# Altium.net
KiCad netlist of a schematic drawn in Altium Designer
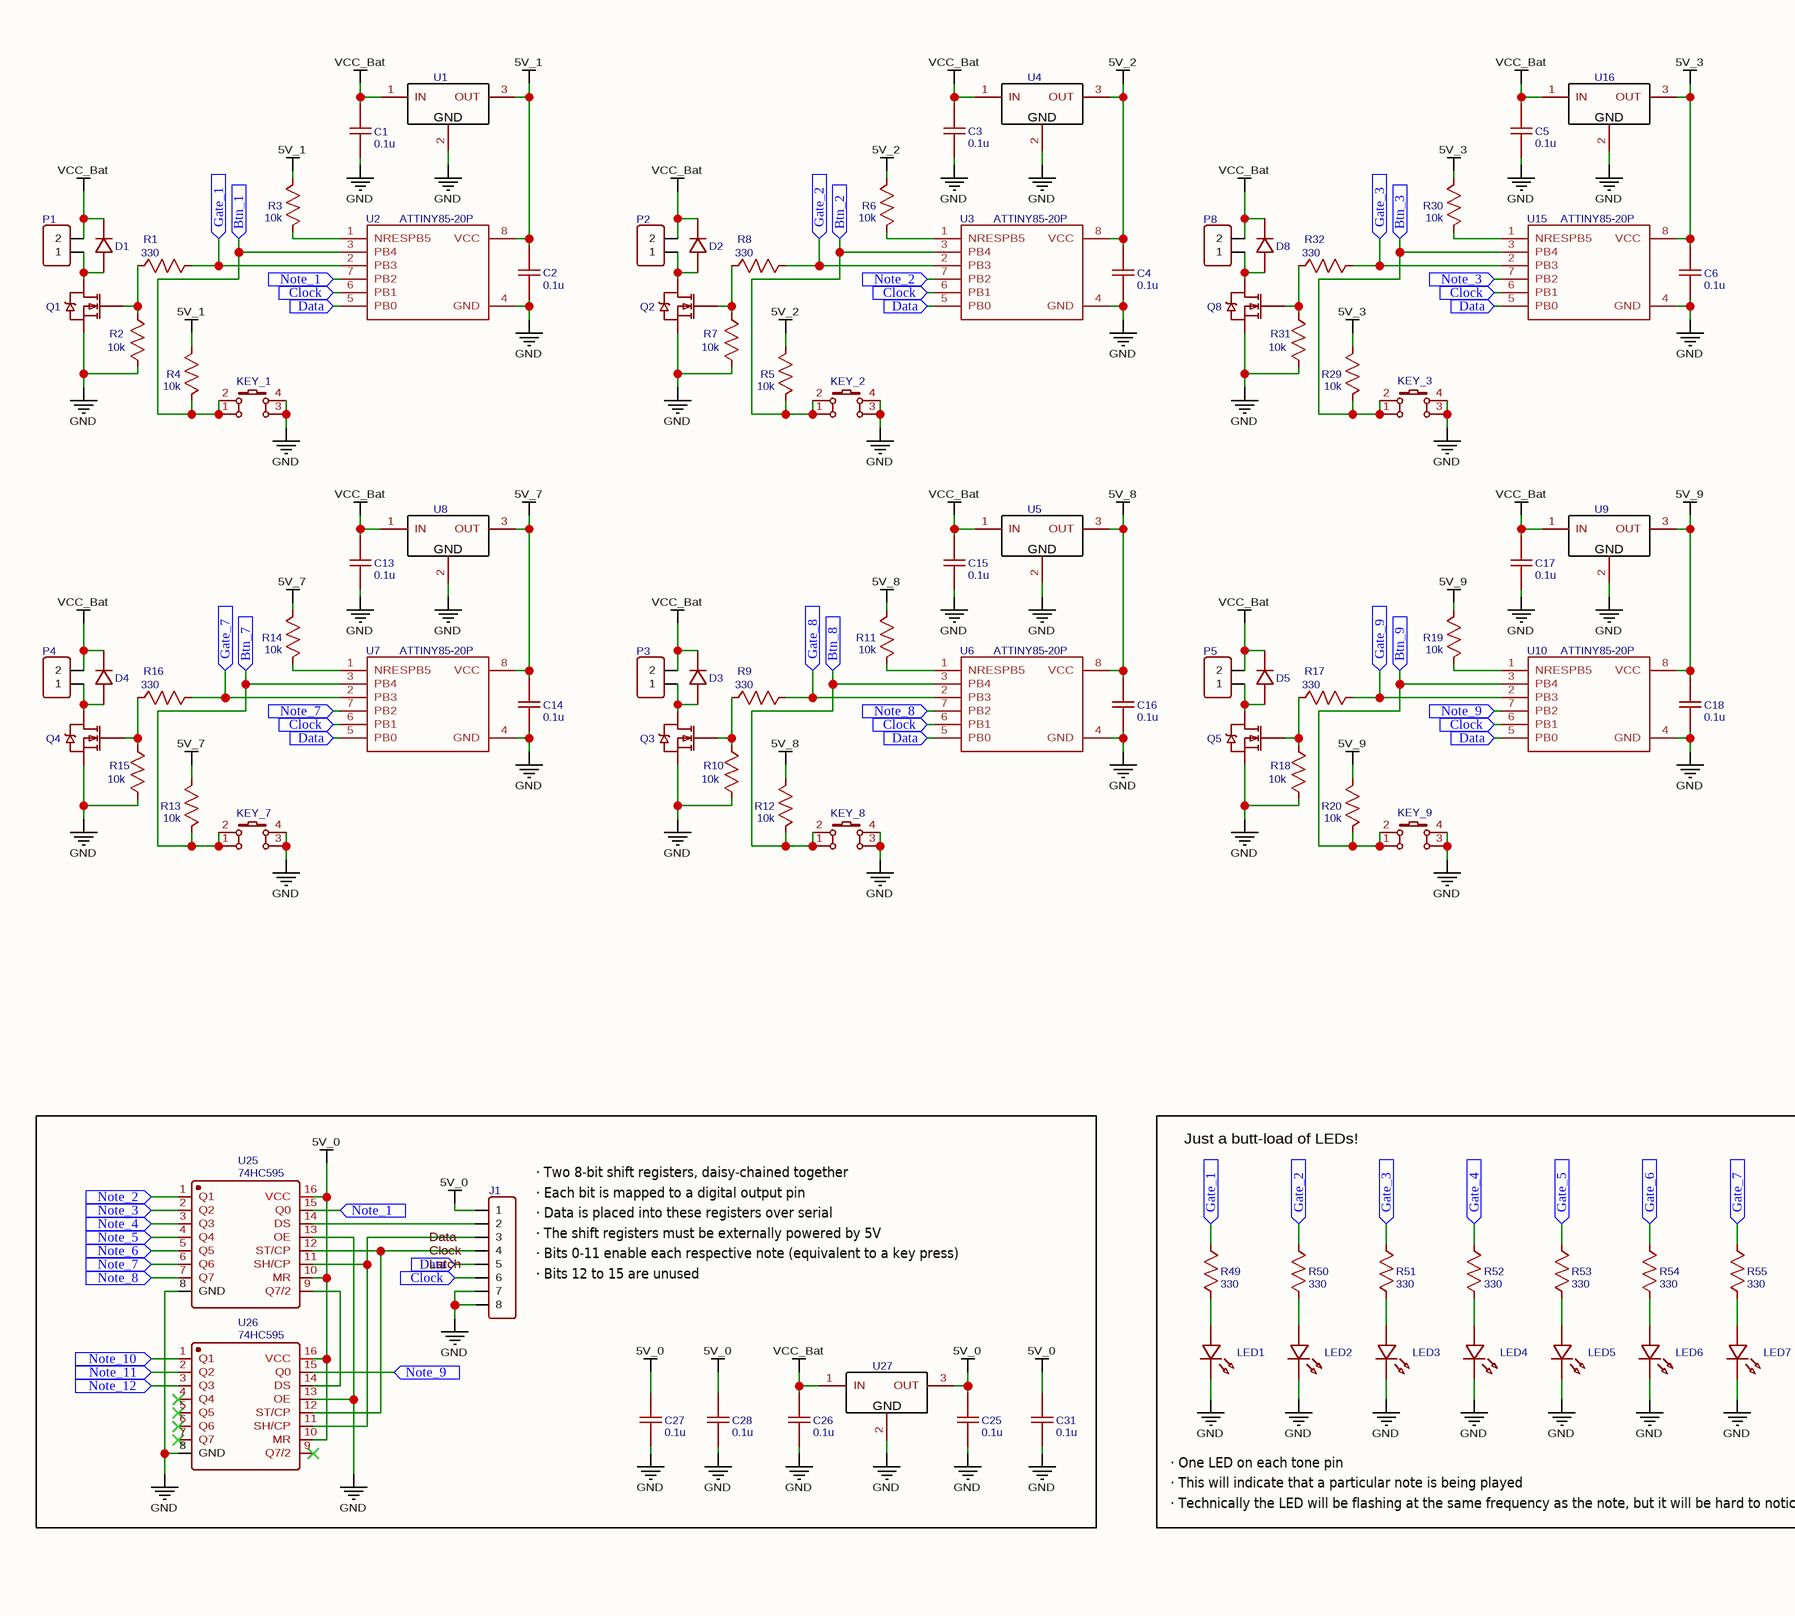
[diagram p0: Altium.schdoc, left]
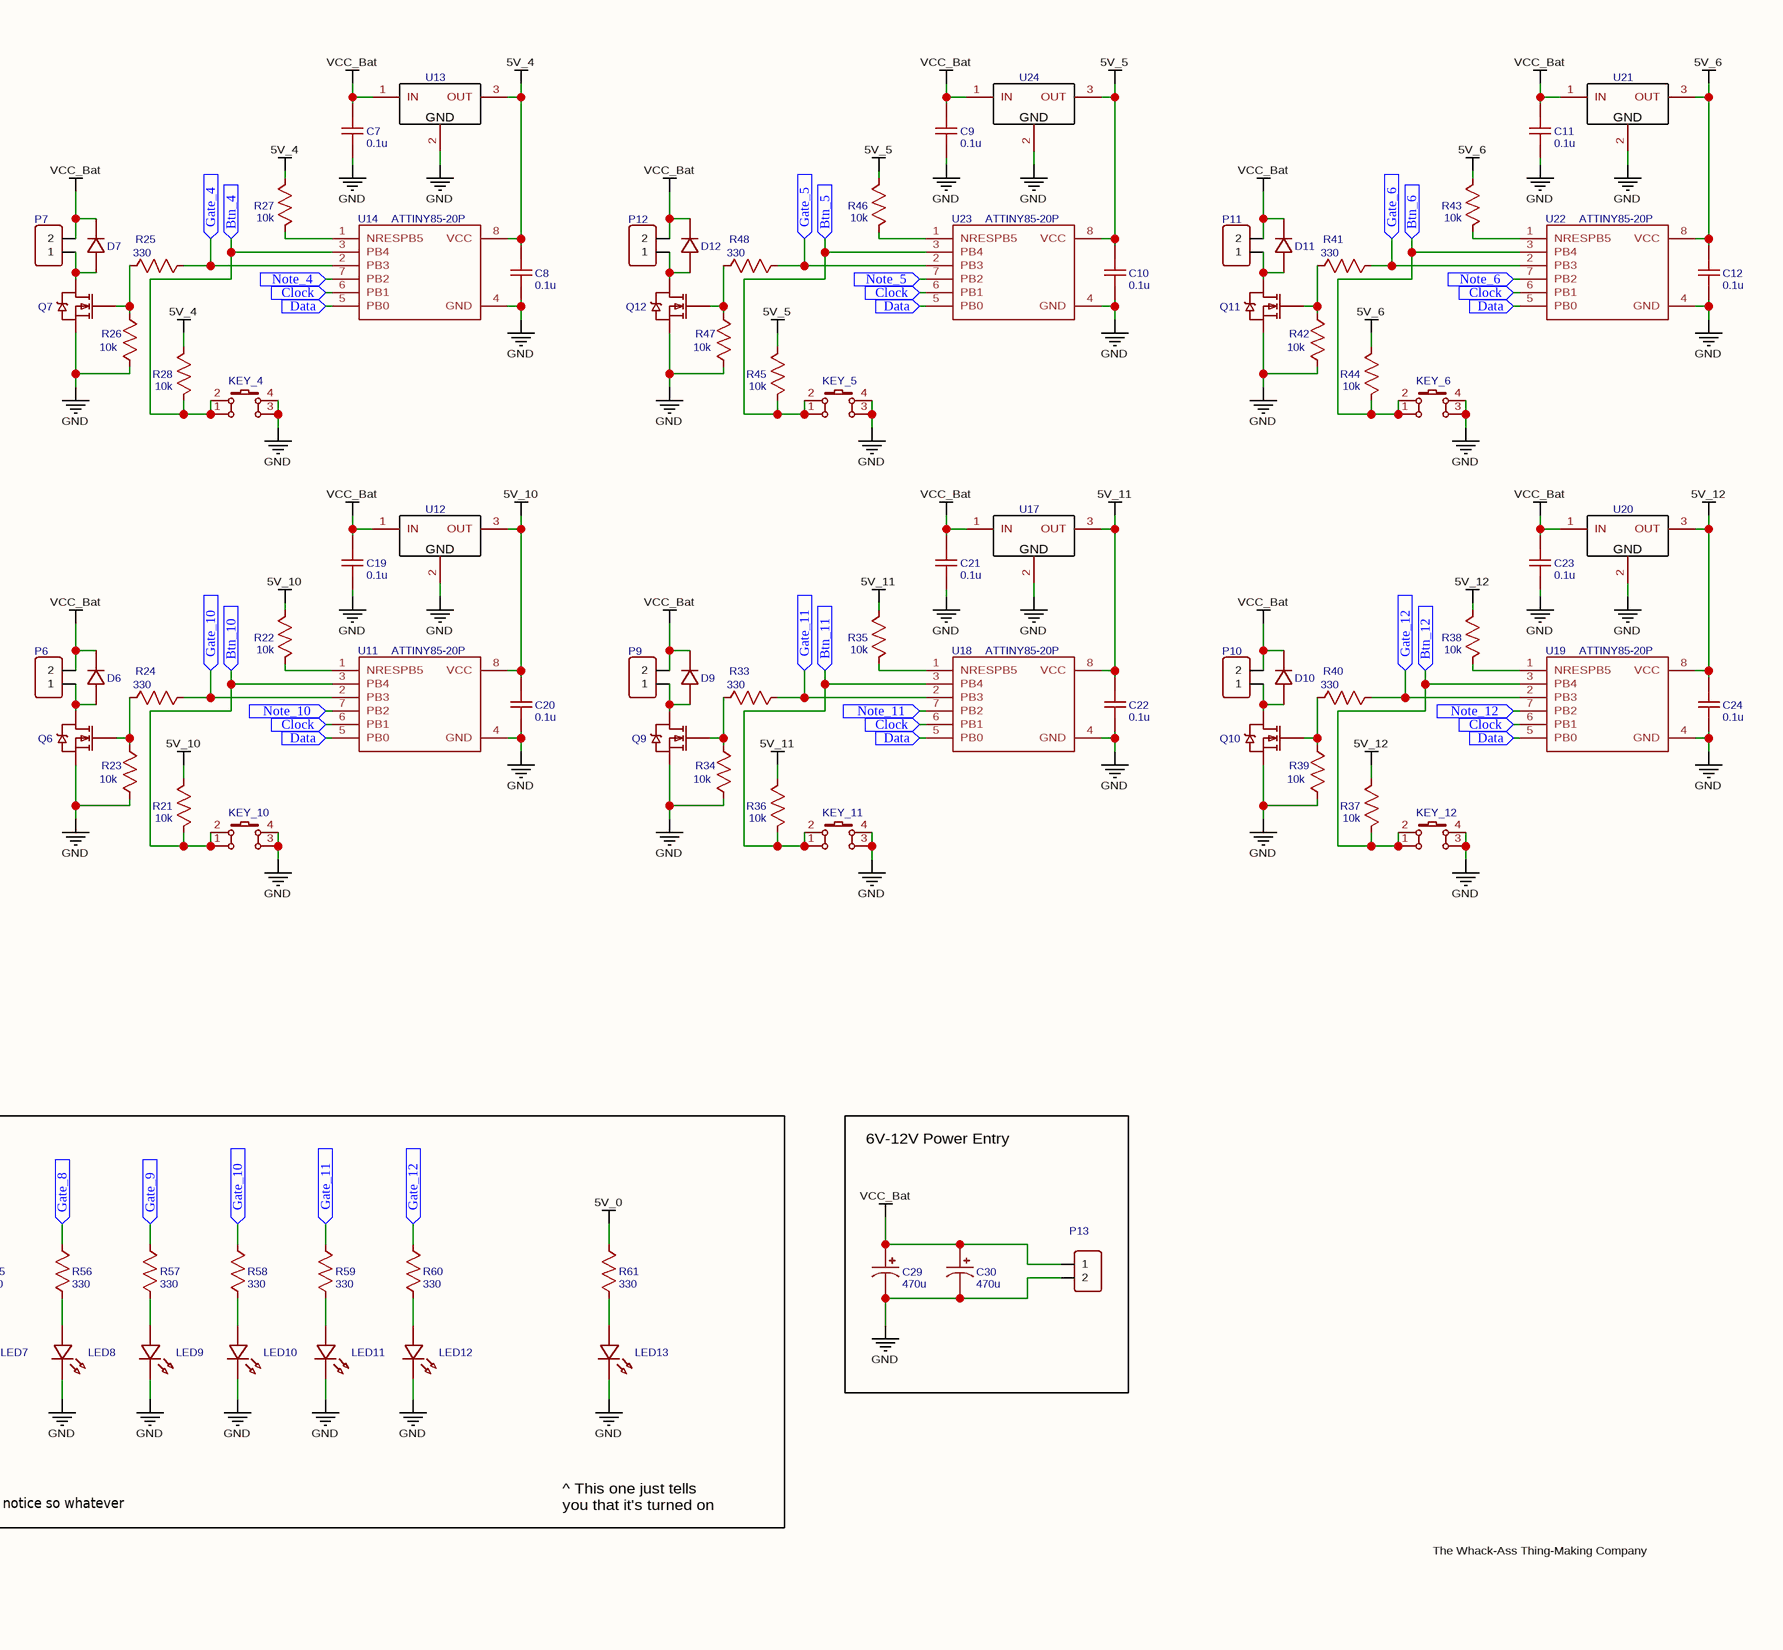
[diagram p1: Altium.schdoc, right]

(export (version "E")
  (design (tool "Eeschema 10.0.6"))
  (components
    (comp (ref "C1")
      (value "0.1u")
      (fields (field (name "CONTRIBUTOR") "LCEDA_Lib"))
      (libsource (lib "altium-import") (part "root_1_0.1u_"))
    )
    (comp (ref "C2")
      (value "0.1u")
      (fields (field (name "CONTRIBUTOR") "LCEDA_Lib"))
      (libsource (lib "altium-import") (part "root_1_0.1u_"))
    )
    (comp (ref "C3")
      (value "0.1u")
      (fields (field (name "CONTRIBUTOR") "LCEDA_Lib"))
      (libsource (lib "altium-import") (part "root_1_0.1u_"))
    )
    (comp (ref "C4")
      (value "0.1u")
      (fields (field (name "CONTRIBUTOR") "LCEDA_Lib"))
      (libsource (lib "altium-import") (part "root_1_0.1u_"))
    )
    (comp (ref "C5")
      (value "0.1u")
      (fields (field (name "CONTRIBUTOR") "LCEDA_Lib"))
      (libsource (lib "altium-import") (part "root_1_0.1u_"))
    )
    (comp (ref "C6")
      (value "0.1u")
      (fields (field (name "CONTRIBUTOR") "LCEDA_Lib"))
      (libsource (lib "altium-import") (part "root_1_0.1u_"))
    )
    (comp (ref "C7")
      (value "0.1u")
      (fields (field (name "CONTRIBUTOR") "LCEDA_Lib"))
      (libsource (lib "altium-import") (part "root_1_0.1u_"))
    )
    (comp (ref "C8")
      (value "0.1u")
      (fields (field (name "CONTRIBUTOR") "LCEDA_Lib"))
      (libsource (lib "altium-import") (part "root_1_0.1u_"))
    )
    (comp (ref "C9")
      (value "0.1u")
      (fields (field (name "CONTRIBUTOR") "LCEDA_Lib"))
      (libsource (lib "altium-import") (part "root_1_0.1u_"))
    )
    (comp (ref "C10")
      (value "0.1u")
      (fields (field (name "CONTRIBUTOR") "LCEDA_Lib"))
      (libsource (lib "altium-import") (part "root_1_0.1u_"))
    )
    (comp (ref "C11")
      (value "0.1u")
      (fields (field (name "CONTRIBUTOR") "LCEDA_Lib"))
      (libsource (lib "altium-import") (part "root_1_0.1u_"))
    )
    (comp (ref "C12")
      (value "0.1u")
      (fields (field (name "CONTRIBUTOR") "LCEDA_Lib"))
      (libsource (lib "altium-import") (part "root_1_0.1u_"))
    )
    (comp (ref "C13")
      (value "0.1u")
      (fields (field (name "CONTRIBUTOR") "LCEDA_Lib"))
      (libsource (lib "altium-import") (part "root_1_0.1u_"))
    )
    (comp (ref "C14")
      (value "0.1u")
      (fields (field (name "CONTRIBUTOR") "LCEDA_Lib"))
      (libsource (lib "altium-import") (part "root_1_0.1u_"))
    )
    (comp (ref "C15")
      (value "0.1u")
      (fields (field (name "CONTRIBUTOR") "LCEDA_Lib"))
      (libsource (lib "altium-import") (part "root_1_0.1u_"))
    )
    (comp (ref "C16")
      (value "0.1u")
      (fields (field (name "CONTRIBUTOR") "LCEDA_Lib"))
      (libsource (lib "altium-import") (part "root_1_0.1u_"))
    )
    (comp (ref "C17")
      (value "0.1u")
      (fields (field (name "CONTRIBUTOR") "LCEDA_Lib"))
      (libsource (lib "altium-import") (part "root_1_0.1u_"))
    )
    (comp (ref "C18")
      (value "0.1u")
      (fields (field (name "CONTRIBUTOR") "LCEDA_Lib"))
      (libsource (lib "altium-import") (part "root_1_0.1u_"))
    )
    (comp (ref "C19")
      (value "0.1u")
      (fields (field (name "CONTRIBUTOR") "LCEDA_Lib"))
      (libsource (lib "altium-import") (part "root_1_0.1u_"))
    )
    (comp (ref "C20")
      (value "0.1u")
      (fields (field (name "CONTRIBUTOR") "LCEDA_Lib"))
      (libsource (lib "altium-import") (part "root_1_0.1u_"))
    )
    (comp (ref "C21")
      (value "0.1u")
      (fields (field (name "CONTRIBUTOR") "LCEDA_Lib"))
      (libsource (lib "altium-import") (part "root_1_0.1u_"))
    )
    (comp (ref "C22")
      (value "0.1u")
      (fields (field (name "CONTRIBUTOR") "LCEDA_Lib"))
      (libsource (lib "altium-import") (part "root_1_0.1u_"))
    )
    (comp (ref "C23")
      (value "0.1u")
      (fields (field (name "CONTRIBUTOR") "LCEDA_Lib"))
      (libsource (lib "altium-import") (part "root_1_0.1u_"))
    )
    (comp (ref "C24")
      (value "0.1u")
      (fields (field (name "CONTRIBUTOR") "LCEDA_Lib"))
      (libsource (lib "altium-import") (part "root_1_0.1u_"))
    )
    (comp (ref "C25")
      (value "0.1u")
      (fields (field (name "CONTRIBUTOR") "LCEDA_Lib"))
      (libsource (lib "altium-import") (part "root_1_0.1u_"))
    )
    (comp (ref "C26")
      (value "0.1u")
      (fields (field (name "CONTRIBUTOR") "LCEDA_Lib"))
      (libsource (lib "altium-import") (part "root_1_0.1u_"))
    )
    (comp (ref "C27")
      (value "0.1u")
      (fields (field (name "CONTRIBUTOR") "LCEDA_Lib"))
      (libsource (lib "altium-import") (part "root_1_0.1u_"))
    )
    (comp (ref "C28")
      (value "0.1u")
      (fields (field (name "CONTRIBUTOR") "LCEDA_Lib"))
      (libsource (lib "altium-import") (part "root_1_0.1u_"))
    )
    (comp (ref "C29")
      (value "470u")
      (fields (field (name "CONTRIBUTOR") "LCEDA_Lib"))
      (libsource (lib "altium-import") (part "root_3_470u_"))
    )
    (comp (ref "C30")
      (value "470u")
      (fields (field (name "CONTRIBUTOR") "LCEDA_Lib"))
      (libsource (lib "altium-import") (part "root_3_470u_"))
    )
    (comp (ref "C31")
      (value "0.1u")
      (fields (field (name "CONTRIBUTOR") "LCEDA_Lib"))
      (libsource (lib "altium-import") (part "root_1_0.1u_"))
    )
    (comp (ref "D1")
      (value "1N4007")
      (fields (field (name "BOM_SUPPLIER PART") "C106903") (field (name "CONTRIBUTOR") "LCEDA_Lib"))
      (libsource (lib "altium-import") (part "root_1_1N4007_"))
    )
    (comp (ref "D2")
      (value "1N4007")
      (fields (field (name "BOM_SUPPLIER PART") "C106903") (field (name "CONTRIBUTOR") "LCEDA_Lib"))
      (libsource (lib "altium-import") (part "root_1_1N4007_"))
    )
    (comp (ref "D3")
      (value "1N4007")
      (fields (field (name "BOM_SUPPLIER PART") "C106903") (field (name "CONTRIBUTOR") "LCEDA_Lib"))
      (libsource (lib "altium-import") (part "root_1_1N4007_"))
    )
    (comp (ref "D4")
      (value "1N4007")
      (fields (field (name "BOM_SUPPLIER PART") "C106903") (field (name "CONTRIBUTOR") "LCEDA_Lib"))
      (libsource (lib "altium-import") (part "root_1_1N4007_"))
    )
    (comp (ref "D5")
      (value "1N4007")
      (fields (field (name "BOM_SUPPLIER PART") "C106903") (field (name "CONTRIBUTOR") "LCEDA_Lib"))
      (libsource (lib "altium-import") (part "root_1_1N4007_"))
    )
    (comp (ref "D6")
      (value "1N4007")
      (fields (field (name "BOM_SUPPLIER PART") "C106903") (field (name "CONTRIBUTOR") "LCEDA_Lib"))
      (libsource (lib "altium-import") (part "root_1_1N4007_"))
    )
    (comp (ref "D7")
      (value "1N4007")
      (fields (field (name "BOM_SUPPLIER PART") "C106903") (field (name "CONTRIBUTOR") "LCEDA_Lib"))
      (libsource (lib "altium-import") (part "root_1_1N4007_"))
    )
    (comp (ref "D8")
      (value "1N4007")
      (fields (field (name "BOM_SUPPLIER PART") "C106903") (field (name "CONTRIBUTOR") "LCEDA_Lib"))
      (libsource (lib "altium-import") (part "root_1_1N4007_"))
    )
    (comp (ref "D9")
      (value "1N4007")
      (fields (field (name "BOM_SUPPLIER PART") "C106903") (field (name "CONTRIBUTOR") "LCEDA_Lib"))
      (libsource (lib "altium-import") (part "root_1_1N4007_"))
    )
    (comp (ref "D10")
      (value "1N4007")
      (fields (field (name "BOM_SUPPLIER PART") "C106903") (field (name "CONTRIBUTOR") "LCEDA_Lib"))
      (libsource (lib "altium-import") (part "root_1_1N4007_"))
    )
    (comp (ref "D11")
      (value "1N4007")
      (fields (field (name "BOM_SUPPLIER PART") "C106903") (field (name "CONTRIBUTOR") "LCEDA_Lib"))
      (libsource (lib "altium-import") (part "root_1_1N4007_"))
    )
    (comp (ref "D12")
      (value "1N4007")
      (fields (field (name "BOM_SUPPLIER PART") "C106903") (field (name "CONTRIBUTOR") "LCEDA_Lib"))
      (libsource (lib "altium-import") (part "root_1_1N4007_"))
    )
    (comp (ref "J1")
      (value "HDR-M-2.54_1x8")
      (fields (field (name "BOM_SUPPLIER PART") "C190820") (field (name "CONTRIBUTOR") "LCEDA_Lib"))
      (libsource (lib "altium-import") (part "root_0_HDR-M-2.54_1x8_"))
    )
    (comp (ref "KEY_1")
      (value "K4-6×6_TH")
      (fields
        (field (name "BOM_SUPPLIER PART") "C136684")
        (field (name "BOM_MANUFACTURER PART") "K2-1102DP-E4SW-04")
        (field (name "CONTRIBUTOR") "LCEDA_Lib")
      )
      (libsource (lib "altium-import") (part "root_0_K4-6×6_TH_"))
    )
    (comp (ref "KEY_2")
      (value "K4-6×6_TH")
      (fields
        (field (name "BOM_SUPPLIER PART") "C136684")
        (field (name "BOM_MANUFACTURER PART") "K2-1102DP-E4SW-04")
        (field (name "CONTRIBUTOR") "LCEDA_Lib")
      )
      (libsource (lib "altium-import") (part "root_0_K4-6×6_TH_"))
    )
    (comp (ref "KEY_3")
      (value "K4-6×6_TH")
      (fields
        (field (name "BOM_SUPPLIER PART") "C136684")
        (field (name "BOM_MANUFACTURER PART") "K2-1102DP-E4SW-04")
        (field (name "CONTRIBUTOR") "LCEDA_Lib")
      )
      (libsource (lib "altium-import") (part "root_0_K4-6×6_TH_"))
    )
    (comp (ref "KEY_4")
      (value "K4-6×6_TH")
      (fields
        (field (name "BOM_SUPPLIER PART") "C136684")
        (field (name "BOM_MANUFACTURER PART") "K2-1102DP-E4SW-04")
        (field (name "CONTRIBUTOR") "LCEDA_Lib")
      )
      (libsource (lib "altium-import") (part "root_0_K4-6×6_TH_"))
    )
    (comp (ref "KEY_5")
      (value "K4-6×6_TH")
      (fields
        (field (name "BOM_SUPPLIER PART") "C136684")
        (field (name "BOM_MANUFACTURER PART") "K2-1102DP-E4SW-04")
        (field (name "CONTRIBUTOR") "LCEDA_Lib")
      )
      (libsource (lib "altium-import") (part "root_0_K4-6×6_TH_"))
    )
    (comp (ref "KEY_6")
      (value "K4-6×6_TH")
      (fields
        (field (name "BOM_SUPPLIER PART") "C136684")
        (field (name "BOM_MANUFACTURER PART") "K2-1102DP-E4SW-04")
        (field (name "CONTRIBUTOR") "LCEDA_Lib")
      )
      (libsource (lib "altium-import") (part "root_0_K4-6×6_TH_"))
    )
    (comp (ref "KEY_7")
      (value "K4-6×6_TH")
      (fields
        (field (name "BOM_SUPPLIER PART") "C136684")
        (field (name "BOM_MANUFACTURER PART") "K2-1102DP-E4SW-04")
        (field (name "CONTRIBUTOR") "LCEDA_Lib")
      )
      (libsource (lib "altium-import") (part "root_0_K4-6×6_TH_"))
    )
    (comp (ref "KEY_8")
      (value "K4-6×6_TH")
      (fields
        (field (name "BOM_SUPPLIER PART") "C136684")
        (field (name "BOM_MANUFACTURER PART") "K2-1102DP-E4SW-04")
        (field (name "CONTRIBUTOR") "LCEDA_Lib")
      )
      (libsource (lib "altium-import") (part "root_0_K4-6×6_TH_"))
    )
    (comp (ref "KEY_9")
      (value "K4-6×6_TH")
      (fields
        (field (name "BOM_SUPPLIER PART") "C136684")
        (field (name "BOM_MANUFACTURER PART") "K2-1102DP-E4SW-04")
        (field (name "CONTRIBUTOR") "LCEDA_Lib")
      )
      (libsource (lib "altium-import") (part "root_0_K4-6×6_TH_"))
    )
    (comp (ref "KEY_10")
      (value "K4-6×6_TH")
      (fields
        (field (name "BOM_SUPPLIER PART") "C136684")
        (field (name "BOM_MANUFACTURER PART") "K2-1102DP-E4SW-04")
        (field (name "CONTRIBUTOR") "LCEDA_Lib")
      )
      (libsource (lib "altium-import") (part "root_0_K4-6×6_TH_"))
    )
    (comp (ref "KEY_11")
      (value "K4-6×6_TH")
      (fields
        (field (name "BOM_SUPPLIER PART") "C136684")
        (field (name "BOM_MANUFACTURER PART") "K2-1102DP-E4SW-04")
        (field (name "CONTRIBUTOR") "LCEDA_Lib")
      )
      (libsource (lib "altium-import") (part "root_0_K4-6×6_TH_"))
    )
    (comp (ref "KEY_12")
      (value "K4-6×6_TH")
      (fields
        (field (name "BOM_SUPPLIER PART") "C136684")
        (field (name "BOM_MANUFACTURER PART") "K2-1102DP-E4SW-04")
        (field (name "CONTRIBUTOR") "LCEDA_Lib")
      )
      (libsource (lib "altium-import") (part "root_0_K4-6×6_TH_"))
    )
    (comp (ref "LED1")
      (value "LED-TH-3mm_R")
      (fields
        (field (name "BOM_MANUFACTURER PART") "204-10SDRD/S530-A3-L")
        (field (name "BOM_SUPPLIER PART") "C84774")
        (field (name "CONTRIBUTOR") "LCEDA_Lib")
      )
      (libsource (lib "altium-import") (part "root_3_LED-TH-3mm_R_"))
    )
    (comp (ref "LED2")
      (value "LED-TH-3mm_R")
      (fields
        (field (name "BOM_MANUFACTURER PART") "204-10SDRD/S530-A3-L")
        (field (name "BOM_SUPPLIER PART") "C84774")
        (field (name "CONTRIBUTOR") "LCEDA_Lib")
      )
      (libsource (lib "altium-import") (part "root_3_LED-TH-3mm_R_"))
    )
    (comp (ref "LED3")
      (value "LED-TH-3mm_R")
      (fields
        (field (name "BOM_MANUFACTURER PART") "204-10SDRD/S530-A3-L")
        (field (name "BOM_SUPPLIER PART") "C84774")
        (field (name "CONTRIBUTOR") "LCEDA_Lib")
      )
      (libsource (lib "altium-import") (part "root_3_LED-TH-3mm_R_"))
    )
    (comp (ref "LED4")
      (value "LED-TH-3mm_R")
      (fields
        (field (name "BOM_MANUFACTURER PART") "204-10SDRD/S530-A3-L")
        (field (name "BOM_SUPPLIER PART") "C84774")
        (field (name "CONTRIBUTOR") "LCEDA_Lib")
      )
      (libsource (lib "altium-import") (part "root_3_LED-TH-3mm_R_"))
    )
    (comp (ref "LED5")
      (value "LED-TH-3mm_R")
      (fields
        (field (name "BOM_MANUFACTURER PART") "204-10SDRD/S530-A3-L")
        (field (name "BOM_SUPPLIER PART") "C84774")
        (field (name "CONTRIBUTOR") "LCEDA_Lib")
      )
      (libsource (lib "altium-import") (part "root_3_LED-TH-3mm_R_"))
    )
    (comp (ref "LED6")
      (value "LED-TH-3mm_R")
      (fields
        (field (name "BOM_MANUFACTURER PART") "204-10SDRD/S530-A3-L")
        (field (name "BOM_SUPPLIER PART") "C84774")
        (field (name "CONTRIBUTOR") "LCEDA_Lib")
      )
      (libsource (lib "altium-import") (part "root_3_LED-TH-3mm_R_"))
    )
    (comp (ref "LED7")
      (value "LED-TH-3mm_R")
      (fields
        (field (name "BOM_MANUFACTURER PART") "204-10SDRD/S530-A3-L")
        (field (name "BOM_SUPPLIER PART") "C84774")
        (field (name "CONTRIBUTOR") "LCEDA_Lib")
      )
      (libsource (lib "altium-import") (part "root_3_LED-TH-3mm_R_"))
    )
    (comp (ref "LED8")
      (value "LED-TH-3mm_R")
      (fields
        (field (name "BOM_MANUFACTURER PART") "204-10SDRD/S530-A3-L")
        (field (name "BOM_SUPPLIER PART") "C84774")
        (field (name "CONTRIBUTOR") "LCEDA_Lib")
      )
      (libsource (lib "altium-import") (part "root_3_LED-TH-3mm_R_"))
    )
    (comp (ref "LED9")
      (value "LED-TH-3mm_R")
      (fields
        (field (name "BOM_MANUFACTURER PART") "204-10SDRD/S530-A3-L")
        (field (name "BOM_SUPPLIER PART") "C84774")
        (field (name "CONTRIBUTOR") "LCEDA_Lib")
      )
      (libsource (lib "altium-import") (part "root_3_LED-TH-3mm_R_"))
    )
    (comp (ref "LED10")
      (value "LED-TH-3mm_R")
      (fields
        (field (name "BOM_MANUFACTURER PART") "204-10SDRD/S530-A3-L")
        (field (name "BOM_SUPPLIER PART") "C84774")
        (field (name "CONTRIBUTOR") "LCEDA_Lib")
      )
      (libsource (lib "altium-import") (part "root_3_LED-TH-3mm_R_"))
    )
    (comp (ref "LED11")
      (value "LED-TH-3mm_R")
      (fields
        (field (name "BOM_MANUFACTURER PART") "204-10SDRD/S530-A3-L")
        (field (name "BOM_SUPPLIER PART") "C84774")
        (field (name "CONTRIBUTOR") "LCEDA_Lib")
      )
      (libsource (lib "altium-import") (part "root_3_LED-TH-3mm_R_"))
    )
    (comp (ref "LED12")
      (value "LED-TH-3mm_R")
      (fields
        (field (name "BOM_MANUFACTURER PART") "204-10SDRD/S530-A3-L")
        (field (name "BOM_SUPPLIER PART") "C84774")
        (field (name "CONTRIBUTOR") "LCEDA_Lib")
      )
      (libsource (lib "altium-import") (part "root_3_LED-TH-3mm_R_"))
    )
    (comp (ref "LED13")
      (value "LED-TH-3mm_G")
      (fields
        (field (name "BOM_MANUFACTURER PART") "204-10SYGD/S530-E3")
        (field (name "BOM_SUPPLIER PART") "C85161")
        (field (name "CONTRIBUTOR") "LCEDA_Lib")
      )
      (libsource (lib "altium-import") (part "root_3_LED-TH-3mm_G_"))
    )
    (comp (ref "P1")
      (value "Magnet 1")
      (fields (field (name "CONTRIBUTOR") "LCEDA_Lib"))
      (libsource (lib "altium-import") (part "root_2_Magnet 1_"))
    )
    (comp (ref "P2")
      (value "Magnet 1")
      (fields (field (name "CONTRIBUTOR") "LCEDA_Lib"))
      (libsource (lib "altium-import") (part "root_2_Magnet 1_"))
    )
    (comp (ref "P3")
      (value "Magnet 1")
      (fields (field (name "CONTRIBUTOR") "LCEDA_Lib"))
      (libsource (lib "altium-import") (part "root_2_Magnet 1_"))
    )
    (comp (ref "P4")
      (value "Magnet 1")
      (fields (field (name "CONTRIBUTOR") "LCEDA_Lib"))
      (libsource (lib "altium-import") (part "root_2_Magnet 1_"))
    )
    (comp (ref "P5")
      (value "Magnet 1")
      (fields (field (name "CONTRIBUTOR") "LCEDA_Lib"))
      (libsource (lib "altium-import") (part "root_2_Magnet 1_"))
    )
    (comp (ref "P6")
      (value "Magnet 1")
      (fields (field (name "CONTRIBUTOR") "LCEDA_Lib"))
      (libsource (lib "altium-import") (part "root_2_Magnet 1_"))
    )
    (comp (ref "P7")
      (value "Magnet 1")
      (fields (field (name "CONTRIBUTOR") "LCEDA_Lib"))
      (libsource (lib "altium-import") (part "root_2_Magnet 1_"))
    )
    (comp (ref "P8")
      (value "Magnet 1")
      (fields (field (name "CONTRIBUTOR") "LCEDA_Lib"))
      (libsource (lib "altium-import") (part "root_2_Magnet 1_"))
    )
    (comp (ref "P9")
      (value "Magnet 1")
      (fields (field (name "CONTRIBUTOR") "LCEDA_Lib"))
      (libsource (lib "altium-import") (part "root_2_Magnet 1_"))
    )
    (comp (ref "P10")
      (value "Magnet 1")
      (fields (field (name "CONTRIBUTOR") "LCEDA_Lib"))
      (libsource (lib "altium-import") (part "root_2_Magnet 1_"))
    )
    (comp (ref "P11")
      (value "Magnet 1")
      (fields (field (name "CONTRIBUTOR") "LCEDA_Lib"))
      (libsource (lib "altium-import") (part "root_2_Magnet 1_"))
    )
    (comp (ref "P12")
      (value "Magnet 1")
      (fields (field (name "CONTRIBUTOR") "LCEDA_Lib"))
      (libsource (lib "altium-import") (part "root_2_Magnet 1_"))
    )
    (comp (ref "P13")
      (value "Magnet 1")
      (fields (field (name "CONTRIBUTOR") "LCEDA_Lib"))
      (libsource (lib "altium-import") (part "root_0_Magnet 1_"))
    )
    (comp (ref "Q1")
      (value "30N06L-TA3-T")
      (fields (field (name "BOM_SUPPLIER PART") "C99961"))
      (libsource (lib "altium-import") (part "root_0_30N06L-TA3-T_"))
    )
    (comp (ref "Q2")
      (value "30N06L-TA3-T")
      (fields (field (name "BOM_SUPPLIER PART") "C99961"))
      (libsource (lib "altium-import") (part "root_0_30N06L-TA3-T_"))
    )
    (comp (ref "Q3")
      (value "30N06L-TA3-T")
      (fields (field (name "BOM_SUPPLIER PART") "C99961"))
      (libsource (lib "altium-import") (part "root_0_30N06L-TA3-T_"))
    )
    (comp (ref "Q4")
      (value "30N06L-TA3-T")
      (fields (field (name "BOM_SUPPLIER PART") "C99961"))
      (libsource (lib "altium-import") (part "root_0_30N06L-TA3-T_"))
    )
    (comp (ref "Q5")
      (value "30N06L-TA3-T")
      (fields (field (name "BOM_SUPPLIER PART") "C99961"))
      (libsource (lib "altium-import") (part "root_0_30N06L-TA3-T_"))
    )
    (comp (ref "Q6")
      (value "30N06L-TA3-T")
      (fields (field (name "BOM_SUPPLIER PART") "C99961"))
      (libsource (lib "altium-import") (part "root_0_30N06L-TA3-T_"))
    )
    (comp (ref "Q7")
      (value "30N06L-TA3-T")
      (fields (field (name "BOM_SUPPLIER PART") "C99961"))
      (libsource (lib "altium-import") (part "root_0_30N06L-TA3-T_"))
    )
    (comp (ref "Q8")
      (value "30N06L-TA3-T")
      (fields (field (name "BOM_SUPPLIER PART") "C99961"))
      (libsource (lib "altium-import") (part "root_0_30N06L-TA3-T_"))
    )
    (comp (ref "Q9")
      (value "30N06L-TA3-T")
      (fields (field (name "BOM_SUPPLIER PART") "C99961"))
      (libsource (lib "altium-import") (part "root_0_30N06L-TA3-T_"))
    )
    (comp (ref "Q10")
      (value "30N06L-TA3-T")
      (fields (field (name "BOM_SUPPLIER PART") "C99961"))
      (libsource (lib "altium-import") (part "root_0_30N06L-TA3-T_"))
    )
    (comp (ref "Q11")
      (value "30N06L-TA3-T")
      (fields (field (name "BOM_SUPPLIER PART") "C99961"))
      (libsource (lib "altium-import") (part "root_0_30N06L-TA3-T_"))
    )
    (comp (ref "Q12")
      (value "30N06L-TA3-T")
      (fields (field (name "BOM_SUPPLIER PART") "C99961"))
      (libsource (lib "altium-import") (part "root_0_30N06L-TA3-T_"))
    )
    (comp (ref "R1")
      (value "330")
      (fields (field (name "CONTRIBUTOR") "LCEDA_Lib"))
      (libsource (lib "altium-import") (part "root_0_330_"))
    )
    (comp (ref "R2")
      (value "10k")
      (fields (field (name "CONTRIBUTOR") "LCEDA_Lib"))
      (libsource (lib "") (part "root_1_10k__1"))
    )
    (comp (ref "R3")
      (value "10k")
      (fields (field (name "CONTRIBUTOR") "LCEDA_Lib"))
      (libsource (lib "altium-import") (part "root_1_10k_"))
    )
    (comp (ref "R4")
      (value "10k")
      (fields (field (name "CONTRIBUTOR") "LCEDA_Lib"))
      (libsource (lib "altium-import") (part "root_1_10k_"))
    )
    (comp (ref "R5")
      (value "10k")
      (fields (field (name "CONTRIBUTOR") "LCEDA_Lib"))
      (libsource (lib "altium-import") (part "root_1_10k_"))
    )
    (comp (ref "R6")
      (value "10k")
      (fields (field (name "CONTRIBUTOR") "LCEDA_Lib"))
      (libsource (lib "altium-import") (part "root_1_10k_"))
    )
    (comp (ref "R7")
      (value "10k")
      (fields (field (name "CONTRIBUTOR") "LCEDA_Lib"))
      (libsource (lib "") (part "root_1_10k__1"))
    )
    (comp (ref "R8")
      (value "330")
      (fields (field (name "CONTRIBUTOR") "LCEDA_Lib"))
      (libsource (lib "altium-import") (part "root_0_330_"))
    )
    (comp (ref "R9")
      (value "330")
      (fields (field (name "CONTRIBUTOR") "LCEDA_Lib"))
      (libsource (lib "altium-import") (part "root_0_330_"))
    )
    (comp (ref "R10")
      (value "10k")
      (fields (field (name "CONTRIBUTOR") "LCEDA_Lib"))
      (libsource (lib "") (part "root_1_10k__1"))
    )
    (comp (ref "R11")
      (value "10k")
      (fields (field (name "CONTRIBUTOR") "LCEDA_Lib"))
      (libsource (lib "altium-import") (part "root_1_10k_"))
    )
    (comp (ref "R12")
      (value "10k")
      (fields (field (name "CONTRIBUTOR") "LCEDA_Lib"))
      (libsource (lib "altium-import") (part "root_1_10k_"))
    )
    (comp (ref "R13")
      (value "10k")
      (fields (field (name "CONTRIBUTOR") "LCEDA_Lib"))
      (libsource (lib "altium-import") (part "root_1_10k_"))
    )
    (comp (ref "R14")
      (value "10k")
      (fields (field (name "CONTRIBUTOR") "LCEDA_Lib"))
      (libsource (lib "altium-import") (part "root_1_10k_"))
    )
    (comp (ref "R15")
      (value "10k")
      (fields (field (name "CONTRIBUTOR") "LCEDA_Lib"))
      (libsource (lib "") (part "root_1_10k__1"))
    )
    (comp (ref "R16")
      (value "330")
      (fields (field (name "CONTRIBUTOR") "LCEDA_Lib"))
      (libsource (lib "altium-import") (part "root_0_330_"))
    )
    (comp (ref "R17")
      (value "330")
      (fields (field (name "CONTRIBUTOR") "LCEDA_Lib"))
      (libsource (lib "altium-import") (part "root_0_330_"))
    )
    (comp (ref "R18")
      (value "10k")
      (fields (field (name "CONTRIBUTOR") "LCEDA_Lib"))
      (libsource (lib "") (part "root_1_10k__1"))
    )
    (comp (ref "R19")
      (value "10k")
      (fields (field (name "CONTRIBUTOR") "LCEDA_Lib"))
      (libsource (lib "altium-import") (part "root_1_10k_"))
    )
    (comp (ref "R20")
      (value "10k")
      (fields (field (name "CONTRIBUTOR") "LCEDA_Lib"))
      (libsource (lib "altium-import") (part "root_1_10k_"))
    )
    (comp (ref "R21")
      (value "10k")
      (fields (field (name "CONTRIBUTOR") "LCEDA_Lib"))
      (libsource (lib "altium-import") (part "root_1_10k_"))
    )
    (comp (ref "R22")
      (value "10k")
      (fields (field (name "CONTRIBUTOR") "LCEDA_Lib"))
      (libsource (lib "altium-import") (part "root_1_10k_"))
    )
    (comp (ref "R23")
      (value "10k")
      (fields (field (name "CONTRIBUTOR") "LCEDA_Lib"))
      (libsource (lib "") (part "root_1_10k__1"))
    )
    (comp (ref "R24")
      (value "330")
      (fields (field (name "CONTRIBUTOR") "LCEDA_Lib"))
      (libsource (lib "altium-import") (part "root_0_330_"))
    )
    (comp (ref "R25")
      (value "330")
      (fields (field (name "CONTRIBUTOR") "LCEDA_Lib"))
      (libsource (lib "altium-import") (part "root_0_330_"))
    )
    (comp (ref "R26")
      (value "10k")
      (fields (field (name "CONTRIBUTOR") "LCEDA_Lib"))
      (libsource (lib "") (part "root_1_10k__1"))
    )
    (comp (ref "R27")
      (value "10k")
      (fields (field (name "CONTRIBUTOR") "LCEDA_Lib"))
      (libsource (lib "altium-import") (part "root_1_10k_"))
    )
    (comp (ref "R28")
      (value "10k")
      (fields (field (name "CONTRIBUTOR") "LCEDA_Lib"))
      (libsource (lib "altium-import") (part "root_1_10k_"))
    )
    (comp (ref "R29")
      (value "10k")
      (fields (field (name "CONTRIBUTOR") "LCEDA_Lib"))
      (libsource (lib "altium-import") (part "root_1_10k_"))
    )
    (comp (ref "R30")
      (value "10k")
      (fields (field (name "CONTRIBUTOR") "LCEDA_Lib"))
      (libsource (lib "altium-import") (part "root_1_10k_"))
    )
    (comp (ref "R31")
      (value "10k")
      (fields (field (name "CONTRIBUTOR") "LCEDA_Lib"))
      (libsource (lib "") (part "root_1_10k__1"))
    )
    (comp (ref "R32")
      (value "330")
      (fields (field (name "CONTRIBUTOR") "LCEDA_Lib"))
      (libsource (lib "altium-import") (part "root_0_330_"))
    )
    (comp (ref "R33")
      (value "330")
      (fields (field (name "CONTRIBUTOR") "LCEDA_Lib"))
      (libsource (lib "altium-import") (part "root_0_330_"))
    )
    (comp (ref "R34")
      (value "10k")
      (fields (field (name "CONTRIBUTOR") "LCEDA_Lib"))
      (libsource (lib "") (part "root_1_10k__1"))
    )
    (comp (ref "R35")
      (value "10k")
      (fields (field (name "CONTRIBUTOR") "LCEDA_Lib"))
      (libsource (lib "altium-import") (part "root_1_10k_"))
    )
    (comp (ref "R36")
      (value "10k")
      (fields (field (name "CONTRIBUTOR") "LCEDA_Lib"))
      (libsource (lib "altium-import") (part "root_1_10k_"))
    )
    (comp (ref "R37")
      (value "10k")
      (fields (field (name "CONTRIBUTOR") "LCEDA_Lib"))
      (libsource (lib "altium-import") (part "root_1_10k_"))
    )
    (comp (ref "R38")
      (value "10k")
      (fields (field (name "CONTRIBUTOR") "LCEDA_Lib"))
      (libsource (lib "altium-import") (part "root_1_10k_"))
    )
    (comp (ref "R39")
      (value "10k")
      (fields (field (name "CONTRIBUTOR") "LCEDA_Lib"))
      (libsource (lib "") (part "root_1_10k__1"))
    )
    (comp (ref "R40")
      (value "330")
      (fields (field (name "CONTRIBUTOR") "LCEDA_Lib"))
      (libsource (lib "altium-import") (part "root_0_330_"))
    )
    (comp (ref "R41")
      (value "330")
      (fields (field (name "CONTRIBUTOR") "LCEDA_Lib"))
      (libsource (lib "altium-import") (part "root_0_330_"))
    )
    (comp (ref "R42")
      (value "10k")
      (fields (field (name "CONTRIBUTOR") "LCEDA_Lib"))
      (libsource (lib "") (part "root_1_10k__1"))
    )
    (comp (ref "R43")
      (value "10k")
      (fields (field (name "CONTRIBUTOR") "LCEDA_Lib"))
      (libsource (lib "altium-import") (part "root_1_10k_"))
    )
    (comp (ref "R44")
      (value "10k")
      (fields (field (name "CONTRIBUTOR") "LCEDA_Lib"))
      (libsource (lib "altium-import") (part "root_1_10k_"))
    )
    (comp (ref "R45")
      (value "10k")
      (fields (field (name "CONTRIBUTOR") "LCEDA_Lib"))
      (libsource (lib "altium-import") (part "root_1_10k_"))
    )
    (comp (ref "R46")
      (value "10k")
      (fields (field (name "CONTRIBUTOR") "LCEDA_Lib"))
      (libsource (lib "altium-import") (part "root_1_10k_"))
    )
    (comp (ref "R47")
      (value "10k")
      (fields (field (name "CONTRIBUTOR") "LCEDA_Lib"))
      (libsource (lib "") (part "root_1_10k__1"))
    )
    (comp (ref "R48")
      (value "330")
      (fields (field (name "CONTRIBUTOR") "LCEDA_Lib"))
      (libsource (lib "altium-import") (part "root_0_330_"))
    )
    (comp (ref "R49")
      (value "330")
      (fields (field (name "CONTRIBUTOR") "LCEDA_Lib"))
      (libsource (lib "altium-import") (part "root_1_330_"))
    )
    (comp (ref "R50")
      (value "330")
      (fields (field (name "CONTRIBUTOR") "LCEDA_Lib"))
      (libsource (lib "altium-import") (part "root_1_330_"))
    )
    (comp (ref "R51")
      (value "330")
      (fields (field (name "CONTRIBUTOR") "LCEDA_Lib"))
      (libsource (lib "altium-import") (part "root_1_330_"))
    )
    (comp (ref "R52")
      (value "330")
      (fields (field (name "CONTRIBUTOR") "LCEDA_Lib"))
      (libsource (lib "altium-import") (part "root_1_330_"))
    )
    (comp (ref "R53")
      (value "330")
      (fields (field (name "CONTRIBUTOR") "LCEDA_Lib"))
      (libsource (lib "altium-import") (part "root_1_330_"))
    )
    (comp (ref "R54")
      (value "330")
      (fields (field (name "CONTRIBUTOR") "LCEDA_Lib"))
      (libsource (lib "altium-import") (part "root_1_330_"))
    )
    (comp (ref "R55")
      (value "330")
      (fields (field (name "CONTRIBUTOR") "LCEDA_Lib"))
      (libsource (lib "altium-import") (part "root_1_330_"))
    )
    (comp (ref "R56")
      (value "330")
      (fields (field (name "CONTRIBUTOR") "LCEDA_Lib"))
      (libsource (lib "altium-import") (part "root_1_330_"))
    )
    (comp (ref "R57")
      (value "330")
      (fields (field (name "CONTRIBUTOR") "LCEDA_Lib"))
      (libsource (lib "altium-import") (part "root_1_330_"))
    )
    (comp (ref "R58")
      (value "330")
      (fields (field (name "CONTRIBUTOR") "LCEDA_Lib"))
      (libsource (lib "altium-import") (part "root_1_330_"))
    )
    (comp (ref "R59")
      (value "330")
      (fields (field (name "CONTRIBUTOR") "LCEDA_Lib"))
      (libsource (lib "altium-import") (part "root_1_330_"))
    )
    (comp (ref "R60")
      (value "330")
      (fields (field (name "CONTRIBUTOR") "LCEDA_Lib"))
      (libsource (lib "altium-import") (part "root_1_330_"))
    )
    (comp (ref "R61")
      (value "330")
      (fields (field (name "CONTRIBUTOR") "LCEDA_Lib"))
      (libsource (lib "altium-import") (part "root_1_330_"))
    )
    (comp (ref "U1")
      (value "7805(TO-220)")
      (fields
        (field (name "BOM_MANUFACTURER PART") "L7805CV-DG")
        (field (name "BOM_SUPPLIER PART") "C3795")
        (field (name "CONTRIBUTOR") "LCEDA_Lib")
      )
      (libsource (lib "altium-import") (part "root_0_7805(TO-220)_"))
    )
    (comp (ref "U2") (value "ATTINY85-20P") (libsource (lib "altium-import") (part "root_2_ATTINY85-20P_")))
    (comp (ref "U3") (value "ATTINY85-20P") (libsource (lib "altium-import") (part "root_2_ATTINY85-20P_")))
    (comp (ref "U4")
      (value "7805(TO-220)")
      (fields
        (field (name "BOM_MANUFACTURER PART") "L7805CV-DG")
        (field (name "BOM_SUPPLIER PART") "C3795")
        (field (name "CONTRIBUTOR") "LCEDA_Lib")
      )
      (libsource (lib "altium-import") (part "root_0_7805(TO-220)_"))
    )
    (comp (ref "U5")
      (value "7805(TO-220)")
      (fields
        (field (name "BOM_MANUFACTURER PART") "L7805CV-DG")
        (field (name "BOM_SUPPLIER PART") "C3795")
        (field (name "CONTRIBUTOR") "LCEDA_Lib")
      )
      (libsource (lib "altium-import") (part "root_0_7805(TO-220)_"))
    )
    (comp (ref "U6") (value "ATTINY85-20P") (libsource (lib "altium-import") (part "root_2_ATTINY85-20P_")))
    (comp (ref "U7") (value "ATTINY85-20P") (libsource (lib "altium-import") (part "root_2_ATTINY85-20P_")))
    (comp (ref "U8")
      (value "7805(TO-220)")
      (fields
        (field (name "BOM_MANUFACTURER PART") "L7805CV-DG")
        (field (name "BOM_SUPPLIER PART") "C3795")
        (field (name "CONTRIBUTOR") "LCEDA_Lib")
      )
      (libsource (lib "altium-import") (part "root_0_7805(TO-220)_"))
    )
    (comp (ref "U9")
      (value "7805(TO-220)")
      (fields
        (field (name "BOM_MANUFACTURER PART") "L7805CV-DG")
        (field (name "BOM_SUPPLIER PART") "C3795")
        (field (name "CONTRIBUTOR") "LCEDA_Lib")
      )
      (libsource (lib "altium-import") (part "root_0_7805(TO-220)_"))
    )
    (comp (ref "U10") (value "ATTINY85-20P") (libsource (lib "altium-import") (part "root_2_ATTINY85-20P_")))
    (comp (ref "U11") (value "ATTINY85-20P") (libsource (lib "altium-import") (part "root_2_ATTINY85-20P_")))
    (comp (ref "U12")
      (value "7805(TO-220)")
      (fields
        (field (name "BOM_MANUFACTURER PART") "L7805CV-DG")
        (field (name "BOM_SUPPLIER PART") "C3795")
        (field (name "CONTRIBUTOR") "LCEDA_Lib")
      )
      (libsource (lib "altium-import") (part "root_0_7805(TO-220)_"))
    )
    (comp (ref "U13")
      (value "7805(TO-220)")
      (fields
        (field (name "BOM_MANUFACTURER PART") "L7805CV-DG")
        (field (name "BOM_SUPPLIER PART") "C3795")
        (field (name "CONTRIBUTOR") "LCEDA_Lib")
      )
      (libsource (lib "altium-import") (part "root_0_7805(TO-220)_"))
    )
    (comp (ref "U14") (value "ATTINY85-20P") (libsource (lib "altium-import") (part "root_2_ATTINY85-20P_")))
    (comp (ref "U15") (value "ATTINY85-20P") (libsource (lib "altium-import") (part "root_2_ATTINY85-20P_")))
    (comp (ref "U16")
      (value "7805(TO-220)")
      (fields
        (field (name "BOM_MANUFACTURER PART") "L7805CV-DG")
        (field (name "BOM_SUPPLIER PART") "C3795")
        (field (name "CONTRIBUTOR") "LCEDA_Lib")
      )
      (libsource (lib "altium-import") (part "root_0_7805(TO-220)_"))
    )
    (comp (ref "U17")
      (value "7805(TO-220)")
      (fields
        (field (name "BOM_MANUFACTURER PART") "L7805CV-DG")
        (field (name "BOM_SUPPLIER PART") "C3795")
        (field (name "CONTRIBUTOR") "LCEDA_Lib")
      )
      (libsource (lib "altium-import") (part "root_0_7805(TO-220)_"))
    )
    (comp (ref "U18") (value "ATTINY85-20P") (libsource (lib "altium-import") (part "root_2_ATTINY85-20P_")))
    (comp (ref "U19") (value "ATTINY85-20P") (libsource (lib "altium-import") (part "root_2_ATTINY85-20P_")))
    (comp (ref "U20")
      (value "7805(TO-220)")
      (fields
        (field (name "BOM_MANUFACTURER PART") "L7805CV-DG")
        (field (name "BOM_SUPPLIER PART") "C3795")
        (field (name "CONTRIBUTOR") "LCEDA_Lib")
      )
      (libsource (lib "altium-import") (part "root_0_7805(TO-220)_"))
    )
    (comp (ref "U21")
      (value "7805(TO-220)")
      (fields
        (field (name "BOM_MANUFACTURER PART") "L7805CV-DG")
        (field (name "BOM_SUPPLIER PART") "C3795")
        (field (name "CONTRIBUTOR") "LCEDA_Lib")
      )
      (libsource (lib "altium-import") (part "root_0_7805(TO-220)_"))
    )
    (comp (ref "U22") (value "ATTINY85-20P") (libsource (lib "altium-import") (part "root_2_ATTINY85-20P_")))
    (comp (ref "U23") (value "ATTINY85-20P") (libsource (lib "altium-import") (part "root_2_ATTINY85-20P_")))
    (comp (ref "U24")
      (value "7805(TO-220)")
      (fields
        (field (name "BOM_MANUFACTURER PART") "L7805CV-DG")
        (field (name "BOM_SUPPLIER PART") "C3795")
        (field (name "CONTRIBUTOR") "LCEDA_Lib")
      )
      (libsource (lib "altium-import") (part "root_0_7805(TO-220)_"))
    )
    (comp (ref "U25") (value "74HC595") (libsource (lib "altium-import") (part "root_0_74HC595_")))
    (comp (ref "U26") (value "74HC595") (libsource (lib "altium-import") (part "root_0_74HC595_")))
    (comp (ref "U27")
      (value "7805(TO-220)")
      (fields
        (field (name "BOM_MANUFACTURER PART") "L7805CV-DG")
        (field (name "BOM_SUPPLIER PART") "C3795")
        (field (name "CONTRIBUTOR") "LCEDA_Lib")
      )
      (libsource (lib "altium-import") (part "root_0_7805(TO-220)_"))
    )
  )
  (nets
    (net (code "1") (name "/Btn_1") (class "Default")
      (node (ref "KEY_1") (pin "1") (pinfunction "1_1") (pintype "passive"))
      (node (ref "KEY_1") (pin "2") (pinfunction "2_2") (pintype "passive"))
      (node (ref "R4") (pin "1") (pinfunction "1_1") (pintype "passive"))
      (node (ref "U2") (pin "3") (pinfunction "PB4_3") (pintype "passive"))
    )
    (net (code "2") (name "/Btn_2") (class "Default")
      (node (ref "KEY_2") (pin "1") (pinfunction "1_1") (pintype "passive"))
      (node (ref "KEY_2") (pin "2") (pinfunction "2_2") (pintype "passive"))
      (node (ref "R5") (pin "1") (pinfunction "1_1") (pintype "passive"))
      (node (ref "U3") (pin "3") (pinfunction "PB4_3") (pintype "passive"))
    )
    (net (code "3") (name "/Btn_3") (class "Default")
      (node (ref "KEY_3") (pin "1") (pinfunction "1_1") (pintype "passive"))
      (node (ref "KEY_3") (pin "2") (pinfunction "2_2") (pintype "passive"))
      (node (ref "R29") (pin "1") (pinfunction "1_1") (pintype "passive"))
      (node (ref "U15") (pin "3") (pinfunction "PB4_3") (pintype "passive"))
    )
    (net (code "4") (name "/Btn_4") (class "Default")
      (node (ref "KEY_4") (pin "1") (pinfunction "1_1") (pintype "passive"))
      (node (ref "KEY_4") (pin "2") (pinfunction "2_2") (pintype "passive"))
      (node (ref "R28") (pin "1") (pinfunction "1_1") (pintype "passive"))
      (node (ref "U14") (pin "3") (pinfunction "PB4_3") (pintype "passive"))
    )
    (net (code "5") (name "/Btn_5") (class "Default")
      (node (ref "KEY_5") (pin "1") (pinfunction "1_1") (pintype "passive"))
      (node (ref "KEY_5") (pin "2") (pinfunction "2_2") (pintype "passive"))
      (node (ref "R45") (pin "1") (pinfunction "1_1") (pintype "passive"))
      (node (ref "U23") (pin "3") (pinfunction "PB4_3") (pintype "passive"))
    )
    (net (code "6") (name "/Btn_6") (class "Default")
      (node (ref "KEY_6") (pin "1") (pinfunction "1_1") (pintype "passive"))
      (node (ref "KEY_6") (pin "2") (pinfunction "2_2") (pintype "passive"))
      (node (ref "R44") (pin "1") (pinfunction "1_1") (pintype "passive"))
      (node (ref "U22") (pin "3") (pinfunction "PB4_3") (pintype "passive"))
    )
    (net (code "7") (name "/Btn_7") (class "Default")
      (node (ref "KEY_7") (pin "1") (pinfunction "1_1") (pintype "passive"))
      (node (ref "KEY_7") (pin "2") (pinfunction "2_2") (pintype "passive"))
      (node (ref "R13") (pin "1") (pinfunction "1_1") (pintype "passive"))
      (node (ref "U7") (pin "3") (pinfunction "PB4_3") (pintype "passive"))
    )
    (net (code "8") (name "/Btn_8") (class "Default")
      (node (ref "KEY_8") (pin "1") (pinfunction "1_1") (pintype "passive"))
      (node (ref "KEY_8") (pin "2") (pinfunction "2_2") (pintype "passive"))
      (node (ref "R12") (pin "1") (pinfunction "1_1") (pintype "passive"))
      (node (ref "U6") (pin "3") (pinfunction "PB4_3") (pintype "passive"))
    )
    (net (code "9") (name "/Btn_9") (class "Default")
      (node (ref "KEY_9") (pin "1") (pinfunction "1_1") (pintype "passive"))
      (node (ref "KEY_9") (pin "2") (pinfunction "2_2") (pintype "passive"))
      (node (ref "R20") (pin "1") (pinfunction "1_1") (pintype "passive"))
      (node (ref "U10") (pin "3") (pinfunction "PB4_3") (pintype "passive"))
    )
    (net (code "10") (name "/Btn_10") (class "Default")
      (node (ref "KEY_10") (pin "1") (pinfunction "1_1") (pintype "passive"))
      (node (ref "KEY_10") (pin "2") (pinfunction "2_2") (pintype "passive"))
      (node (ref "R21") (pin "1") (pinfunction "1_1") (pintype "passive"))
      (node (ref "U11") (pin "3") (pinfunction "PB4_3") (pintype "passive"))
    )
    (net (code "11") (name "/Btn_11") (class "Default")
      (node (ref "KEY_11") (pin "1") (pinfunction "1_1") (pintype "passive"))
      (node (ref "KEY_11") (pin "2") (pinfunction "2_2") (pintype "passive"))
      (node (ref "R36") (pin "1") (pinfunction "1_1") (pintype "passive"))
      (node (ref "U18") (pin "3") (pinfunction "PB4_3") (pintype "passive"))
    )
    (net (code "12") (name "/Btn_12") (class "Default")
      (node (ref "KEY_12") (pin "1") (pinfunction "1_1") (pintype "passive"))
      (node (ref "KEY_12") (pin "2") (pinfunction "2_2") (pintype "passive"))
      (node (ref "R37") (pin "1") (pinfunction "1_1") (pintype "passive"))
      (node (ref "U19") (pin "3") (pinfunction "PB4_3") (pintype "passive"))
    )
    (net (code "13") (name "/Clock") (class "Default")
      (node (ref "J1") (pin "6") (pinfunction "6_6") (pintype "passive"))
      (node (ref "U10") (pin "6") (pinfunction "PB1_6") (pintype "passive"))
      (node (ref "U11") (pin "6") (pinfunction "PB1_6") (pintype "passive"))
      (node (ref "U14") (pin "6") (pinfunction "PB1_6") (pintype "passive"))
      (node (ref "U15") (pin "6") (pinfunction "PB1_6") (pintype "passive"))
      (node (ref "U18") (pin "6") (pinfunction "PB1_6") (pintype "passive"))
      (node (ref "U19") (pin "6") (pinfunction "PB1_6") (pintype "passive"))
      (node (ref "U2") (pin "6") (pinfunction "PB1_6") (pintype "passive"))
      (node (ref "U22") (pin "6") (pinfunction "PB1_6") (pintype "passive"))
      (node (ref "U23") (pin "6") (pinfunction "PB1_6") (pintype "passive"))
      (node (ref "U3") (pin "6") (pinfunction "PB1_6") (pintype "passive"))
      (node (ref "U6") (pin "6") (pinfunction "PB1_6") (pintype "passive"))
      (node (ref "U7") (pin "6") (pinfunction "PB1_6") (pintype "passive"))
    )
    (net (code "14") (name "/Data") (class "Default")
      (node (ref "J1") (pin "5") (pinfunction "5_5") (pintype "passive"))
      (node (ref "U10") (pin "5") (pinfunction "PB0_5") (pintype "passive"))
      (node (ref "U11") (pin "5") (pinfunction "PB0_5") (pintype "passive"))
      (node (ref "U14") (pin "5") (pinfunction "PB0_5") (pintype "passive"))
      (node (ref "U15") (pin "5") (pinfunction "PB0_5") (pintype "passive"))
      (node (ref "U18") (pin "5") (pinfunction "PB0_5") (pintype "passive"))
      (node (ref "U19") (pin "5") (pinfunction "PB0_5") (pintype "passive"))
      (node (ref "U2") (pin "5") (pinfunction "PB0_5") (pintype "passive"))
      (node (ref "U22") (pin "5") (pinfunction "PB0_5") (pintype "passive"))
      (node (ref "U23") (pin "5") (pinfunction "PB0_5") (pintype "passive"))
      (node (ref "U3") (pin "5") (pinfunction "PB0_5") (pintype "passive"))
      (node (ref "U6") (pin "5") (pinfunction "PB0_5") (pintype "passive"))
      (node (ref "U7") (pin "5") (pinfunction "PB0_5") (pintype "passive"))
    )
    (net (code "15") (name "/Gate_1") (class "Default")
      (node (ref "R1") (pin "2") (pinfunction "2_2") (pintype "passive"))
      (node (ref "R49") (pin "2") (pinfunction "2_2") (pintype "passive"))
      (node (ref "U2") (pin "2") (pinfunction "PB3_2") (pintype "passive"))
    )
    (net (code "16") (name "/Gate_2") (class "Default")
      (node (ref "R50") (pin "2") (pinfunction "2_2") (pintype "passive"))
      (node (ref "R8") (pin "2") (pinfunction "2_2") (pintype "passive"))
      (node (ref "U3") (pin "2") (pinfunction "PB3_2") (pintype "passive"))
    )
    (net (code "17") (name "/Gate_3") (class "Default")
      (node (ref "R32") (pin "2") (pinfunction "2_2") (pintype "passive"))
      (node (ref "R51") (pin "2") (pinfunction "2_2") (pintype "passive"))
      (node (ref "U15") (pin "2") (pinfunction "PB3_2") (pintype "passive"))
    )
    (net (code "18") (name "/Gate_4") (class "Default")
      (node (ref "R25") (pin "2") (pinfunction "2_2") (pintype "passive"))
      (node (ref "R52") (pin "2") (pinfunction "2_2") (pintype "passive"))
      (node (ref "U14") (pin "2") (pinfunction "PB3_2") (pintype "passive"))
    )
    (net (code "19") (name "/Gate_5") (class "Default")
      (node (ref "R48") (pin "2") (pinfunction "2_2") (pintype "passive"))
      (node (ref "R53") (pin "2") (pinfunction "2_2") (pintype "passive"))
      (node (ref "U23") (pin "2") (pinfunction "PB3_2") (pintype "passive"))
    )
    (net (code "20") (name "/Gate_6") (class "Default")
      (node (ref "R41") (pin "2") (pinfunction "2_2") (pintype "passive"))
      (node (ref "R54") (pin "2") (pinfunction "2_2") (pintype "passive"))
      (node (ref "U22") (pin "2") (pinfunction "PB3_2") (pintype "passive"))
    )
    (net (code "21") (name "/Gate_7") (class "Default")
      (node (ref "R16") (pin "2") (pinfunction "2_2") (pintype "passive"))
      (node (ref "R55") (pin "2") (pinfunction "2_2") (pintype "passive"))
      (node (ref "U7") (pin "2") (pinfunction "PB3_2") (pintype "passive"))
    )
    (net (code "22") (name "/Gate_8") (class "Default")
      (node (ref "R56") (pin "2") (pinfunction "2_2") (pintype "passive"))
      (node (ref "R9") (pin "2") (pinfunction "2_2") (pintype "passive"))
      (node (ref "U6") (pin "2") (pinfunction "PB3_2") (pintype "passive"))
    )
    (net (code "23") (name "/Gate_9") (class "Default")
      (node (ref "R17") (pin "2") (pinfunction "2_2") (pintype "passive"))
      (node (ref "R57") (pin "2") (pinfunction "2_2") (pintype "passive"))
      (node (ref "U10") (pin "2") (pinfunction "PB3_2") (pintype "passive"))
    )
    (net (code "24") (name "/Gate_10") (class "Default")
      (node (ref "R24") (pin "2") (pinfunction "2_2") (pintype "passive"))
      (node (ref "R58") (pin "2") (pinfunction "2_2") (pintype "passive"))
      (node (ref "U11") (pin "2") (pinfunction "PB3_2") (pintype "passive"))
    )
    (net (code "25") (name "/Gate_11") (class "Default")
      (node (ref "R33") (pin "2") (pinfunction "2_2") (pintype "passive"))
      (node (ref "R59") (pin "2") (pinfunction "2_2") (pintype "passive"))
      (node (ref "U18") (pin "2") (pinfunction "PB3_2") (pintype "passive"))
    )
    (net (code "26") (name "/Gate_12") (class "Default")
      (node (ref "R40") (pin "2") (pinfunction "2_2") (pintype "passive"))
      (node (ref "R60") (pin "2") (pinfunction "2_2") (pintype "passive"))
      (node (ref "U19") (pin "2") (pinfunction "PB3_2") (pintype "passive"))
    )
    (net (code "27") (name "/Note_1") (class "Default")
      (node (ref "U2") (pin "7") (pinfunction "PB2_7") (pintype "passive"))
      (node (ref "U25") (pin "15") (pinfunction "Q0_15") (pintype "passive"))
    )
    (net (code "28") (name "/Note_2") (class "Default")
      (node (ref "U25") (pin "1") (pinfunction "Q1_1") (pintype "passive"))
      (node (ref "U3") (pin "7") (pinfunction "PB2_7") (pintype "passive"))
    )
    (net (code "29") (name "/Note_3") (class "Default")
      (node (ref "U15") (pin "7") (pinfunction "PB2_7") (pintype "passive"))
      (node (ref "U25") (pin "2") (pinfunction "Q2_2") (pintype "passive"))
    )
    (net (code "30") (name "/Note_4") (class "Default")
      (node (ref "U14") (pin "7") (pinfunction "PB2_7") (pintype "passive"))
      (node (ref "U25") (pin "3") (pinfunction "Q3_3") (pintype "passive"))
    )
    (net (code "31") (name "/Note_5") (class "Default")
      (node (ref "U23") (pin "7") (pinfunction "PB2_7") (pintype "passive"))
      (node (ref "U25") (pin "4") (pinfunction "Q4_4") (pintype "passive"))
    )
    (net (code "32") (name "/Note_6") (class "Default")
      (node (ref "U22") (pin "7") (pinfunction "PB2_7") (pintype "passive"))
      (node (ref "U25") (pin "5") (pinfunction "Q5_5") (pintype "passive"))
    )
    (net (code "33") (name "/Note_7") (class "Default")
      (node (ref "U25") (pin "6") (pinfunction "Q6_6") (pintype "passive"))
      (node (ref "U7") (pin "7") (pinfunction "PB2_7") (pintype "passive"))
    )
    (net (code "34") (name "/Note_8") (class "Default")
      (node (ref "U25") (pin "7") (pinfunction "Q7_7") (pintype "passive"))
      (node (ref "U6") (pin "7") (pinfunction "PB2_7") (pintype "passive"))
    )
    (net (code "35") (name "/Note_9") (class "Default")
      (node (ref "U10") (pin "7") (pinfunction "PB2_7") (pintype "passive"))
      (node (ref "U26") (pin "15") (pinfunction "Q0_15") (pintype "passive"))
    )
    (net (code "36") (name "/Note_10") (class "Default")
      (node (ref "U11") (pin "7") (pinfunction "PB2_7") (pintype "passive"))
      (node (ref "U26") (pin "1") (pinfunction "Q1_1") (pintype "passive"))
    )
    (net (code "37") (name "/Note_11") (class "Default")
      (node (ref "U18") (pin "7") (pinfunction "PB2_7") (pintype "passive"))
      (node (ref "U26") (pin "2") (pinfunction "Q2_2") (pintype "passive"))
    )
    (net (code "38") (name "/Note_12") (class "Default")
      (node (ref "U19") (pin "7") (pinfunction "PB2_7") (pintype "passive"))
      (node (ref "U26") (pin "3") (pinfunction "Q3_3") (pintype "passive"))
    )
    (net (code "39") (name "5V_0") (class "Default")
      (node (ref "C25") (pin "2") (pinfunction "2_2") (pintype "passive"))
      (node (ref "C27") (pin "2") (pinfunction "2_2") (pintype "passive"))
      (node (ref "C28") (pin "2") (pinfunction "2_2") (pintype "passive"))
      (node (ref "C31") (pin "2") (pinfunction "2_2") (pintype "passive"))
      (node (ref "J1") (pin "1") (pinfunction "1_1") (pintype "passive"))
      (node (ref "R61") (pin "2") (pinfunction "2_2") (pintype "passive"))
      (node (ref "U25") (pin "10") (pinfunction "MR_10") (pintype "passive"))
      (node (ref "U25") (pin "16") (pinfunction "VCC_16") (pintype "passive"))
      (node (ref "U26") (pin "10") (pinfunction "MR_10") (pintype "passive"))
      (node (ref "U26") (pin "16") (pinfunction "VCC_16") (pintype "passive"))
      (node (ref "U27") (pin "3") (pinfunction "OUT_3") (pintype "passive"))
    )
    (net (code "40") (name "5V_1") (class "Default")
      (node (ref "C2") (pin "2") (pinfunction "2_2") (pintype "passive"))
      (node (ref "R3") (pin "2") (pinfunction "2_2") (pintype "passive"))
      (node (ref "R4") (pin "2") (pinfunction "2_2") (pintype "passive"))
      (node (ref "U1") (pin "3") (pinfunction "OUT_3") (pintype "passive"))
      (node (ref "U2") (pin "8") (pinfunction "VCC_8") (pintype "passive"))
    )
    (net (code "41") (name "5V_2") (class "Default")
      (node (ref "C4") (pin "2") (pinfunction "2_2") (pintype "passive"))
      (node (ref "R5") (pin "2") (pinfunction "2_2") (pintype "passive"))
      (node (ref "R6") (pin "2") (pinfunction "2_2") (pintype "passive"))
      (node (ref "U3") (pin "8") (pinfunction "VCC_8") (pintype "passive"))
      (node (ref "U4") (pin "3") (pinfunction "OUT_3") (pintype "passive"))
    )
    (net (code "42") (name "5V_3") (class "Default")
      (node (ref "C6") (pin "2") (pinfunction "2_2") (pintype "passive"))
      (node (ref "R29") (pin "2") (pinfunction "2_2") (pintype "passive"))
      (node (ref "R30") (pin "2") (pinfunction "2_2") (pintype "passive"))
      (node (ref "U15") (pin "8") (pinfunction "VCC_8") (pintype "passive"))
      (node (ref "U16") (pin "3") (pinfunction "OUT_3") (pintype "passive"))
    )
    (net (code "43") (name "5V_4") (class "Default")
      (node (ref "C8") (pin "2") (pinfunction "2_2") (pintype "passive"))
      (node (ref "R27") (pin "2") (pinfunction "2_2") (pintype "passive"))
      (node (ref "R28") (pin "2") (pinfunction "2_2") (pintype "passive"))
      (node (ref "U13") (pin "3") (pinfunction "OUT_3") (pintype "passive"))
      (node (ref "U14") (pin "8") (pinfunction "VCC_8") (pintype "passive"))
    )
    (net (code "44") (name "5V_5") (class "Default")
      (node (ref "C10") (pin "2") (pinfunction "2_2") (pintype "passive"))
      (node (ref "R45") (pin "2") (pinfunction "2_2") (pintype "passive"))
      (node (ref "R46") (pin "2") (pinfunction "2_2") (pintype "passive"))
      (node (ref "U23") (pin "8") (pinfunction "VCC_8") (pintype "passive"))
      (node (ref "U24") (pin "3") (pinfunction "OUT_3") (pintype "passive"))
    )
    (net (code "45") (name "5V_6") (class "Default")
      (node (ref "C12") (pin "2") (pinfunction "2_2") (pintype "passive"))
      (node (ref "R43") (pin "2") (pinfunction "2_2") (pintype "passive"))
      (node (ref "R44") (pin "2") (pinfunction "2_2") (pintype "passive"))
      (node (ref "U21") (pin "3") (pinfunction "OUT_3") (pintype "passive"))
      (node (ref "U22") (pin "8") (pinfunction "VCC_8") (pintype "passive"))
    )
    (net (code "46") (name "5V_7") (class "Default")
      (node (ref "C14") (pin "2") (pinfunction "2_2") (pintype "passive"))
      (node (ref "R13") (pin "2") (pinfunction "2_2") (pintype "passive"))
      (node (ref "R14") (pin "2") (pinfunction "2_2") (pintype "passive"))
      (node (ref "U7") (pin "8") (pinfunction "VCC_8") (pintype "passive"))
      (node (ref "U8") (pin "3") (pinfunction "OUT_3") (pintype "passive"))
    )
    (net (code "47") (name "5V_8") (class "Default")
      (node (ref "C16") (pin "2") (pinfunction "2_2") (pintype "passive"))
      (node (ref "R11") (pin "2") (pinfunction "2_2") (pintype "passive"))
      (node (ref "R12") (pin "2") (pinfunction "2_2") (pintype "passive"))
      (node (ref "U5") (pin "3") (pinfunction "OUT_3") (pintype "passive"))
      (node (ref "U6") (pin "8") (pinfunction "VCC_8") (pintype "passive"))
    )
    (net (code "48") (name "5V_9") (class "Default")
      (node (ref "C18") (pin "2") (pinfunction "2_2") (pintype "passive"))
      (node (ref "R19") (pin "2") (pinfunction "2_2") (pintype "passive"))
      (node (ref "R20") (pin "2") (pinfunction "2_2") (pintype "passive"))
      (node (ref "U10") (pin "8") (pinfunction "VCC_8") (pintype "passive"))
      (node (ref "U9") (pin "3") (pinfunction "OUT_3") (pintype "passive"))
    )
    (net (code "49") (name "5V_10") (class "Default")
      (node (ref "C20") (pin "2") (pinfunction "2_2") (pintype "passive"))
      (node (ref "R21") (pin "2") (pinfunction "2_2") (pintype "passive"))
      (node (ref "R22") (pin "2") (pinfunction "2_2") (pintype "passive"))
      (node (ref "U11") (pin "8") (pinfunction "VCC_8") (pintype "passive"))
      (node (ref "U12") (pin "3") (pinfunction "OUT_3") (pintype "passive"))
    )
    (net (code "50") (name "5V_11") (class "Default")
      (node (ref "C22") (pin "2") (pinfunction "2_2") (pintype "passive"))
      (node (ref "R35") (pin "2") (pinfunction "2_2") (pintype "passive"))
      (node (ref "R36") (pin "2") (pinfunction "2_2") (pintype "passive"))
      (node (ref "U17") (pin "3") (pinfunction "OUT_3") (pintype "passive"))
      (node (ref "U18") (pin "8") (pinfunction "VCC_8") (pintype "passive"))
    )
    (net (code "51") (name "5V_12") (class "Default")
      (node (ref "C24") (pin "2") (pinfunction "2_2") (pintype "passive"))
      (node (ref "R37") (pin "2") (pinfunction "2_2") (pintype "passive"))
      (node (ref "R38") (pin "2") (pinfunction "2_2") (pintype "passive"))
      (node (ref "U19") (pin "8") (pinfunction "VCC_8") (pintype "passive"))
      (node (ref "U20") (pin "3") (pinfunction "OUT_3") (pintype "passive"))
    )
    (net (code "52") (name "GND") (class "Default")
      (node (ref "C1") (pin "1") (pinfunction "1_1") (pintype "passive"))
      (node (ref "C10") (pin "1") (pinfunction "1_1") (pintype "passive"))
      (node (ref "C11") (pin "1") (pinfunction "1_1") (pintype "passive"))
      (node (ref "C12") (pin "1") (pinfunction "1_1") (pintype "passive"))
      (node (ref "C13") (pin "1") (pinfunction "1_1") (pintype "passive"))
      (node (ref "C14") (pin "1") (pinfunction "1_1") (pintype "passive"))
      (node (ref "C15") (pin "1") (pinfunction "1_1") (pintype "passive"))
      (node (ref "C16") (pin "1") (pinfunction "1_1") (pintype "passive"))
      (node (ref "C17") (pin "1") (pinfunction "1_1") (pintype "passive"))
      (node (ref "C18") (pin "1") (pinfunction "1_1") (pintype "passive"))
      (node (ref "C19") (pin "1") (pinfunction "1_1") (pintype "passive"))
      (node (ref "C2") (pin "1") (pinfunction "1_1") (pintype "passive"))
      (node (ref "C20") (pin "1") (pinfunction "1_1") (pintype "passive"))
      (node (ref "C21") (pin "1") (pinfunction "1_1") (pintype "passive"))
      (node (ref "C22") (pin "1") (pinfunction "1_1") (pintype "passive"))
      (node (ref "C23") (pin "1") (pinfunction "1_1") (pintype "passive"))
      (node (ref "C24") (pin "1") (pinfunction "1_1") (pintype "passive"))
      (node (ref "C25") (pin "1") (pinfunction "1_1") (pintype "passive"))
      (node (ref "C26") (pin "1") (pinfunction "1_1") (pintype "passive"))
      (node (ref "C27") (pin "1") (pinfunction "1_1") (pintype "passive"))
      (node (ref "C28") (pin "1") (pinfunction "1_1") (pintype "passive"))
      (node (ref "C29") (pin "2") (pinfunction "2_2") (pintype "passive"))
      (node (ref "C3") (pin "1") (pinfunction "1_1") (pintype "passive"))
      (node (ref "C30") (pin "2") (pinfunction "2_2") (pintype "passive"))
      (node (ref "C31") (pin "1") (pinfunction "1_1") (pintype "passive"))
      (node (ref "C4") (pin "1") (pinfunction "1_1") (pintype "passive"))
      (node (ref "C5") (pin "1") (pinfunction "1_1") (pintype "passive"))
      (node (ref "C6") (pin "1") (pinfunction "1_1") (pintype "passive"))
      (node (ref "C7") (pin "1") (pinfunction "1_1") (pintype "passive"))
      (node (ref "C8") (pin "1") (pinfunction "1_1") (pintype "passive"))
      (node (ref "C9") (pin "1") (pinfunction "1_1") (pintype "passive"))
      (node (ref "J1") (pin "7") (pinfunction "7_7") (pintype "passive"))
      (node (ref "J1") (pin "8") (pinfunction "8_8") (pintype "passive"))
      (node (ref "KEY_1") (pin "3") (pinfunction "3_3") (pintype "passive"))
      (node (ref "KEY_1") (pin "4") (pinfunction "4_4") (pintype "passive"))
      (node (ref "KEY_10") (pin "3") (pinfunction "3_3") (pintype "passive"))
      (node (ref "KEY_10") (pin "4") (pinfunction "4_4") (pintype "passive"))
      (node (ref "KEY_11") (pin "3") (pinfunction "3_3") (pintype "passive"))
      (node (ref "KEY_11") (pin "4") (pinfunction "4_4") (pintype "passive"))
      (node (ref "KEY_12") (pin "3") (pinfunction "3_3") (pintype "passive"))
      (node (ref "KEY_12") (pin "4") (pinfunction "4_4") (pintype "passive"))
      (node (ref "KEY_2") (pin "3") (pinfunction "3_3") (pintype "passive"))
      (node (ref "KEY_2") (pin "4") (pinfunction "4_4") (pintype "passive"))
      (node (ref "KEY_3") (pin "3") (pinfunction "3_3") (pintype "passive"))
      (node (ref "KEY_3") (pin "4") (pinfunction "4_4") (pintype "passive"))
      (node (ref "KEY_4") (pin "3") (pinfunction "3_3") (pintype "passive"))
      (node (ref "KEY_4") (pin "4") (pinfunction "4_4") (pintype "passive"))
      (node (ref "KEY_5") (pin "3") (pinfunction "3_3") (pintype "passive"))
      (node (ref "KEY_5") (pin "4") (pinfunction "4_4") (pintype "passive"))
      (node (ref "KEY_6") (pin "3") (pinfunction "3_3") (pintype "passive"))
      (node (ref "KEY_6") (pin "4") (pinfunction "4_4") (pintype "passive"))
      (node (ref "KEY_7") (pin "3") (pinfunction "3_3") (pintype "passive"))
      (node (ref "KEY_7") (pin "4") (pinfunction "4_4") (pintype "passive"))
      (node (ref "KEY_8") (pin "3") (pinfunction "3_3") (pintype "passive"))
      (node (ref "KEY_8") (pin "4") (pinfunction "4_4") (pintype "passive"))
      (node (ref "KEY_9") (pin "3") (pinfunction "3_3") (pintype "passive"))
      (node (ref "KEY_9") (pin "4") (pinfunction "4_4") (pintype "passive"))
      (node (ref "LED1") (pin "2") (pinfunction "2_2") (pintype "passive"))
      (node (ref "LED10") (pin "2") (pinfunction "2_2") (pintype "passive"))
      (node (ref "LED11") (pin "2") (pinfunction "2_2") (pintype "passive"))
      (node (ref "LED12") (pin "2") (pinfunction "2_2") (pintype "passive"))
      (node (ref "LED13") (pin "2") (pinfunction "2_2") (pintype "passive"))
      (node (ref "LED2") (pin "2") (pinfunction "2_2") (pintype "passive"))
      (node (ref "LED3") (pin "2") (pinfunction "2_2") (pintype "passive"))
      (node (ref "LED4") (pin "2") (pinfunction "2_2") (pintype "passive"))
      (node (ref "LED5") (pin "2") (pinfunction "2_2") (pintype "passive"))
      (node (ref "LED6") (pin "2") (pinfunction "2_2") (pintype "passive"))
      (node (ref "LED7") (pin "2") (pinfunction "2_2") (pintype "passive"))
      (node (ref "LED8") (pin "2") (pinfunction "2_2") (pintype "passive"))
      (node (ref "LED9") (pin "2") (pinfunction "2_2") (pintype "passive"))
      (node (ref "P13") (pin "2") (pinfunction "2_2") (pintype "passive"))
      (node (ref "Q1") (pin "3") (pinfunction "S_3") (pintype "passive"))
      (node (ref "Q10") (pin "3") (pinfunction "S_3") (pintype "passive"))
      (node (ref "Q11") (pin "3") (pinfunction "S_3") (pintype "passive"))
      (node (ref "Q12") (pin "3") (pinfunction "S_3") (pintype "passive"))
      (node (ref "Q2") (pin "3") (pinfunction "S_3") (pintype "passive"))
      (node (ref "Q3") (pin "3") (pinfunction "S_3") (pintype "passive"))
      (node (ref "Q4") (pin "3") (pinfunction "S_3") (pintype "passive"))
      (node (ref "Q5") (pin "3") (pinfunction "S_3") (pintype "passive"))
      (node (ref "Q6") (pin "3") (pinfunction "S_3") (pintype "passive"))
      (node (ref "Q7") (pin "3") (pinfunction "S_3") (pintype "passive"))
      (node (ref "Q8") (pin "3") (pinfunction "S_3") (pintype "passive"))
      (node (ref "Q9") (pin "3") (pinfunction "S_3") (pintype "passive"))
      (node (ref "R10") (pin "1") (pinfunction "1_1") (pintype "passive"))
      (node (ref "R15") (pin "1") (pinfunction "1_1") (pintype "passive"))
      (node (ref "R18") (pin "1") (pinfunction "1_1") (pintype "passive"))
      (node (ref "R2") (pin "1") (pinfunction "1_1") (pintype "passive"))
      (node (ref "R23") (pin "1") (pinfunction "1_1") (pintype "passive"))
      (node (ref "R26") (pin "1") (pinfunction "1_1") (pintype "passive"))
      (node (ref "R31") (pin "1") (pinfunction "1_1") (pintype "passive"))
      (node (ref "R34") (pin "1") (pinfunction "1_1") (pintype "passive"))
      (node (ref "R39") (pin "1") (pinfunction "1_1") (pintype "passive"))
      (node (ref "R42") (pin "1") (pinfunction "1_1") (pintype "passive"))
      (node (ref "R47") (pin "1") (pinfunction "1_1") (pintype "passive"))
      (node (ref "R7") (pin "1") (pinfunction "1_1") (pintype "passive"))
      (node (ref "U1") (pin "2") (pinfunction "GND_2") (pintype "passive"))
      (node (ref "U10") (pin "4") (pinfunction "GND_4") (pintype "passive"))
      (node (ref "U11") (pin "4") (pinfunction "GND_4") (pintype "passive"))
      (node (ref "U12") (pin "2") (pinfunction "GND_2") (pintype "passive"))
      (node (ref "U13") (pin "2") (pinfunction "GND_2") (pintype "passive"))
      (node (ref "U14") (pin "4") (pinfunction "GND_4") (pintype "passive"))
      (node (ref "U15") (pin "4") (pinfunction "GND_4") (pintype "passive"))
      (node (ref "U16") (pin "2") (pinfunction "GND_2") (pintype "passive"))
      (node (ref "U17") (pin "2") (pinfunction "GND_2") (pintype "passive"))
      (node (ref "U18") (pin "4") (pinfunction "GND_4") (pintype "passive"))
      (node (ref "U19") (pin "4") (pinfunction "GND_4") (pintype "passive"))
      (node (ref "U2") (pin "4") (pinfunction "GND_4") (pintype "passive"))
      (node (ref "U20") (pin "2") (pinfunction "GND_2") (pintype "passive"))
      (node (ref "U21") (pin "2") (pinfunction "GND_2") (pintype "passive"))
      (node (ref "U22") (pin "4") (pinfunction "GND_4") (pintype "passive"))
      (node (ref "U23") (pin "4") (pinfunction "GND_4") (pintype "passive"))
      (node (ref "U24") (pin "2") (pinfunction "GND_2") (pintype "passive"))
      (node (ref "U25") (pin "13") (pinfunction "OE_13") (pintype "passive"))
      (node (ref "U25") (pin "8") (pinfunction "GND_8") (pintype "passive"))
      (node (ref "U26") (pin "13") (pinfunction "OE_13") (pintype "passive"))
      (node (ref "U26") (pin "8") (pinfunction "GND_8") (pintype "passive"))
      (node (ref "U27") (pin "2") (pinfunction "GND_2") (pintype "passive"))
      (node (ref "U3") (pin "4") (pinfunction "GND_4") (pintype "passive"))
      (node (ref "U4") (pin "2") (pinfunction "GND_2") (pintype "passive"))
      (node (ref "U5") (pin "2") (pinfunction "GND_2") (pintype "passive"))
      (node (ref "U6") (pin "4") (pinfunction "GND_4") (pintype "passive"))
      (node (ref "U7") (pin "4") (pinfunction "GND_4") (pintype "passive"))
      (node (ref "U8") (pin "2") (pinfunction "GND_2") (pintype "passive"))
      (node (ref "U9") (pin "2") (pinfunction "GND_2") (pintype "passive"))
    )
    (net (code "53") (name "Net-(LED1-Pad1)") (class "Default")
      (node (ref "LED1") (pin "1") (pinfunction "1_1") (pintype "passive"))
      (node (ref "R49") (pin "1") (pinfunction "1_1") (pintype "passive"))
    )
    (net (code "54") (name "Net-(LED2-Pad1)") (class "Default")
      (node (ref "LED2") (pin "1") (pinfunction "1_1") (pintype "passive"))
      (node (ref "R50") (pin "1") (pinfunction "1_1") (pintype "passive"))
    )
    (net (code "55") (name "Net-(LED3-Pad1)") (class "Default")
      (node (ref "LED3") (pin "1") (pinfunction "1_1") (pintype "passive"))
      (node (ref "R51") (pin "1") (pinfunction "1_1") (pintype "passive"))
    )
    (net (code "56") (name "Net-(LED4-Pad1)") (class "Default")
      (node (ref "LED4") (pin "1") (pinfunction "1_1") (pintype "passive"))
      (node (ref "R52") (pin "1") (pinfunction "1_1") (pintype "passive"))
    )
    (net (code "57") (name "Net-(LED5-Pad1)") (class "Default")
      (node (ref "LED5") (pin "1") (pinfunction "1_1") (pintype "passive"))
      (node (ref "R53") (pin "1") (pinfunction "1_1") (pintype "passive"))
    )
    (net (code "58") (name "Net-(LED6-Pad1)") (class "Default")
      (node (ref "LED6") (pin "1") (pinfunction "1_1") (pintype "passive"))
      (node (ref "R54") (pin "1") (pinfunction "1_1") (pintype "passive"))
    )
    (net (code "59") (name "Net-(LED7-Pad1)") (class "Default")
      (node (ref "LED7") (pin "1") (pinfunction "1_1") (pintype "passive"))
      (node (ref "R55") (pin "1") (pinfunction "1_1") (pintype "passive"))
    )
    (net (code "60") (name "Net-(LED8-Pad1)") (class "Default")
      (node (ref "LED8") (pin "1") (pinfunction "1_1") (pintype "passive"))
      (node (ref "R56") (pin "1") (pinfunction "1_1") (pintype "passive"))
    )
    (net (code "61") (name "Net-(LED9-Pad1)") (class "Default")
      (node (ref "LED9") (pin "1") (pinfunction "1_1") (pintype "passive"))
      (node (ref "R57") (pin "1") (pinfunction "1_1") (pintype "passive"))
    )
    (net (code "62") (name "Net-(LED10-Pad1)") (class "Default")
      (node (ref "LED10") (pin "1") (pinfunction "1_1") (pintype "passive"))
      (node (ref "R58") (pin "1") (pinfunction "1_1") (pintype "passive"))
    )
    (net (code "63") (name "Net-(LED11-Pad1)") (class "Default")
      (node (ref "LED11") (pin "1") (pinfunction "1_1") (pintype "passive"))
      (node (ref "R59") (pin "1") (pinfunction "1_1") (pintype "passive"))
    )
    (net (code "64") (name "Net-(LED12-Pad1)") (class "Default")
      (node (ref "LED12") (pin "1") (pinfunction "1_1") (pintype "passive"))
      (node (ref "R60") (pin "1") (pinfunction "1_1") (pintype "passive"))
    )
    (net (code "65") (name "Net-(LED13-Pad1)") (class "Default")
      (node (ref "LED13") (pin "1") (pinfunction "1_1") (pintype "passive"))
      (node (ref "R61") (pin "1") (pinfunction "1_1") (pintype "passive"))
    )
    (net (code "66") (name "Net-(Q1-D)") (class "Default")
      (node (ref "D1") (pin "2") (pinfunction "2_2") (pintype "passive"))
      (node (ref "P1") (pin "1") (pinfunction "1_1") (pintype "passive"))
      (node (ref "Q1") (pin "2") (pinfunction "D_2") (pintype "passive"))
    )
    (net (code "67") (name "Net-(Q1-G)") (class "Default")
      (node (ref "Q1") (pin "1") (pinfunction "G_1") (pintype "passive"))
      (node (ref "R1") (pin "1") (pinfunction "1_1") (pintype "passive"))
      (node (ref "R2") (pin "2") (pinfunction "2_2") (pintype "passive"))
    )
    (net (code "68") (name "Net-(Q2-D)") (class "Default")
      (node (ref "D2") (pin "2") (pinfunction "2_2") (pintype "passive"))
      (node (ref "P2") (pin "1") (pinfunction "1_1") (pintype "passive"))
      (node (ref "Q2") (pin "2") (pinfunction "D_2") (pintype "passive"))
    )
    (net (code "69") (name "Net-(Q2-G)") (class "Default")
      (node (ref "Q2") (pin "1") (pinfunction "G_1") (pintype "passive"))
      (node (ref "R7") (pin "2") (pinfunction "2_2") (pintype "passive"))
      (node (ref "R8") (pin "1") (pinfunction "1_1") (pintype "passive"))
    )
    (net (code "70") (name "Net-(Q3-D)") (class "Default")
      (node (ref "D3") (pin "2") (pinfunction "2_2") (pintype "passive"))
      (node (ref "P3") (pin "1") (pinfunction "1_1") (pintype "passive"))
      (node (ref "Q3") (pin "2") (pinfunction "D_2") (pintype "passive"))
    )
    (net (code "71") (name "Net-(Q3-G)") (class "Default")
      (node (ref "Q3") (pin "1") (pinfunction "G_1") (pintype "passive"))
      (node (ref "R10") (pin "2") (pinfunction "2_2") (pintype "passive"))
      (node (ref "R9") (pin "1") (pinfunction "1_1") (pintype "passive"))
    )
    (net (code "72") (name "Net-(Q4-D)") (class "Default")
      (node (ref "D4") (pin "2") (pinfunction "2_2") (pintype "passive"))
      (node (ref "P4") (pin "1") (pinfunction "1_1") (pintype "passive"))
      (node (ref "Q4") (pin "2") (pinfunction "D_2") (pintype "passive"))
    )
    (net (code "73") (name "Net-(Q4-G)") (class "Default")
      (node (ref "Q4") (pin "1") (pinfunction "G_1") (pintype "passive"))
      (node (ref "R15") (pin "2") (pinfunction "2_2") (pintype "passive"))
      (node (ref "R16") (pin "1") (pinfunction "1_1") (pintype "passive"))
    )
    (net (code "74") (name "Net-(Q5-D)") (class "Default")
      (node (ref "D5") (pin "2") (pinfunction "2_2") (pintype "passive"))
      (node (ref "P5") (pin "1") (pinfunction "1_1") (pintype "passive"))
      (node (ref "Q5") (pin "2") (pinfunction "D_2") (pintype "passive"))
    )
    (net (code "75") (name "Net-(Q5-G)") (class "Default")
      (node (ref "Q5") (pin "1") (pinfunction "G_1") (pintype "passive"))
      (node (ref "R17") (pin "1") (pinfunction "1_1") (pintype "passive"))
      (node (ref "R18") (pin "2") (pinfunction "2_2") (pintype "passive"))
    )
    (net (code "76") (name "Net-(Q6-D)") (class "Default")
      (node (ref "D6") (pin "2") (pinfunction "2_2") (pintype "passive"))
      (node (ref "P6") (pin "1") (pinfunction "1_1") (pintype "passive"))
      (node (ref "Q6") (pin "2") (pinfunction "D_2") (pintype "passive"))
    )
    (net (code "77") (name "Net-(Q6-G)") (class "Default")
      (node (ref "Q6") (pin "1") (pinfunction "G_1") (pintype "passive"))
      (node (ref "R23") (pin "2") (pinfunction "2_2") (pintype "passive"))
      (node (ref "R24") (pin "1") (pinfunction "1_1") (pintype "passive"))
    )
    (net (code "78") (name "Net-(Q7-D)") (class "Default")
      (node (ref "D7") (pin "2") (pinfunction "2_2") (pintype "passive"))
      (node (ref "P7") (pin "1") (pinfunction "1_1") (pintype "passive"))
      (node (ref "Q7") (pin "2") (pinfunction "D_2") (pintype "passive"))
    )
    (net (code "79") (name "Net-(Q7-G)") (class "Default")
      (node (ref "Q7") (pin "1") (pinfunction "G_1") (pintype "passive"))
      (node (ref "R25") (pin "1") (pinfunction "1_1") (pintype "passive"))
      (node (ref "R26") (pin "2") (pinfunction "2_2") (pintype "passive"))
    )
    (net (code "80") (name "Net-(Q8-D)") (class "Default")
      (node (ref "D8") (pin "2") (pinfunction "2_2") (pintype "passive"))
      (node (ref "P8") (pin "1") (pinfunction "1_1") (pintype "passive"))
      (node (ref "Q8") (pin "2") (pinfunction "D_2") (pintype "passive"))
    )
    (net (code "81") (name "Net-(Q8-G)") (class "Default")
      (node (ref "Q8") (pin "1") (pinfunction "G_1") (pintype "passive"))
      (node (ref "R31") (pin "2") (pinfunction "2_2") (pintype "passive"))
      (node (ref "R32") (pin "1") (pinfunction "1_1") (pintype "passive"))
    )
    (net (code "82") (name "Net-(Q9-D)") (class "Default")
      (node (ref "D9") (pin "2") (pinfunction "2_2") (pintype "passive"))
      (node (ref "P9") (pin "1") (pinfunction "1_1") (pintype "passive"))
      (node (ref "Q9") (pin "2") (pinfunction "D_2") (pintype "passive"))
    )
    (net (code "83") (name "Net-(Q9-G)") (class "Default")
      (node (ref "Q9") (pin "1") (pinfunction "G_1") (pintype "passive"))
      (node (ref "R33") (pin "1") (pinfunction "1_1") (pintype "passive"))
      (node (ref "R34") (pin "2") (pinfunction "2_2") (pintype "passive"))
    )
    (net (code "84") (name "Net-(Q10-D)") (class "Default")
      (node (ref "D10") (pin "2") (pinfunction "2_2") (pintype "passive"))
      (node (ref "P10") (pin "1") (pinfunction "1_1") (pintype "passive"))
      (node (ref "Q10") (pin "2") (pinfunction "D_2") (pintype "passive"))
    )
    (net (code "85") (name "Net-(Q10-G)") (class "Default")
      (node (ref "Q10") (pin "1") (pinfunction "G_1") (pintype "passive"))
      (node (ref "R39") (pin "2") (pinfunction "2_2") (pintype "passive"))
      (node (ref "R40") (pin "1") (pinfunction "1_1") (pintype "passive"))
    )
    (net (code "86") (name "Net-(Q11-D)") (class "Default")
      (node (ref "D11") (pin "2") (pinfunction "2_2") (pintype "passive"))
      (node (ref "P11") (pin "1") (pinfunction "1_1") (pintype "passive"))
      (node (ref "Q11") (pin "2") (pinfunction "D_2") (pintype "passive"))
    )
    (net (code "87") (name "Net-(Q11-G)") (class "Default")
      (node (ref "Q11") (pin "1") (pinfunction "G_1") (pintype "passive"))
      (node (ref "R41") (pin "1") (pinfunction "1_1") (pintype "passive"))
      (node (ref "R42") (pin "2") (pinfunction "2_2") (pintype "passive"))
    )
    (net (code "88") (name "Net-(Q12-D)") (class "Default")
      (node (ref "D12") (pin "2") (pinfunction "2_2") (pintype "passive"))
      (node (ref "P12") (pin "1") (pinfunction "1_1") (pintype "passive"))
      (node (ref "Q12") (pin "2") (pinfunction "D_2") (pintype "passive"))
    )
    (net (code "89") (name "Net-(Q12-G)") (class "Default")
      (node (ref "Q12") (pin "1") (pinfunction "G_1") (pintype "passive"))
      (node (ref "R47") (pin "2") (pinfunction "2_2") (pintype "passive"))
      (node (ref "R48") (pin "1") (pinfunction "1_1") (pintype "passive"))
    )
    (net (code "90") (name "Net-(U2-NRESPB5)") (class "Default")
      (node (ref "R3") (pin "1") (pinfunction "1_1") (pintype "passive"))
      (node (ref "U2") (pin "1") (pinfunction "NRESPB5_1") (pintype "passive"))
    )
    (net (code "91") (name "Net-(U3-NRESPB5)") (class "Default")
      (node (ref "R6") (pin "1") (pinfunction "1_1") (pintype "passive"))
      (node (ref "U3") (pin "1") (pinfunction "NRESPB5_1") (pintype "passive"))
    )
    (net (code "92") (name "Net-(U6-NRESPB5)") (class "Default")
      (node (ref "R11") (pin "1") (pinfunction "1_1") (pintype "passive"))
      (node (ref "U6") (pin "1") (pinfunction "NRESPB5_1") (pintype "passive"))
    )
    (net (code "93") (name "Net-(U7-NRESPB5)") (class "Default")
      (node (ref "R14") (pin "1") (pinfunction "1_1") (pintype "passive"))
      (node (ref "U7") (pin "1") (pinfunction "NRESPB5_1") (pintype "passive"))
    )
    (net (code "94") (name "Net-(U10-NRESPB5)") (class "Default")
      (node (ref "R19") (pin "1") (pinfunction "1_1") (pintype "passive"))
      (node (ref "U10") (pin "1") (pinfunction "NRESPB5_1") (pintype "passive"))
    )
    (net (code "95") (name "Net-(U11-NRESPB5)") (class "Default")
      (node (ref "R22") (pin "1") (pinfunction "1_1") (pintype "passive"))
      (node (ref "U11") (pin "1") (pinfunction "NRESPB5_1") (pintype "passive"))
    )
    (net (code "96") (name "Net-(U14-NRESPB5)") (class "Default")
      (node (ref "R27") (pin "1") (pinfunction "1_1") (pintype "passive"))
      (node (ref "U14") (pin "1") (pinfunction "NRESPB5_1") (pintype "passive"))
    )
    (net (code "97") (name "Net-(U15-NRESPB5)") (class "Default")
      (node (ref "R30") (pin "1") (pinfunction "1_1") (pintype "passive"))
      (node (ref "U15") (pin "1") (pinfunction "NRESPB5_1") (pintype "passive"))
    )
    (net (code "98") (name "Net-(U18-NRESPB5)") (class "Default")
      (node (ref "R35") (pin "1") (pinfunction "1_1") (pintype "passive"))
      (node (ref "U18") (pin "1") (pinfunction "NRESPB5_1") (pintype "passive"))
    )
    (net (code "99") (name "Net-(U19-NRESPB5)") (class "Default")
      (node (ref "R38") (pin "1") (pinfunction "1_1") (pintype "passive"))
      (node (ref "U19") (pin "1") (pinfunction "NRESPB5_1") (pintype "passive"))
    )
    (net (code "100") (name "Net-(U22-NRESPB5)") (class "Default")
      (node (ref "R43") (pin "1") (pinfunction "1_1") (pintype "passive"))
      (node (ref "U22") (pin "1") (pinfunction "NRESPB5_1") (pintype "passive"))
    )
    (net (code "101") (name "Net-(U23-NRESPB5)") (class "Default")
      (node (ref "R46") (pin "1") (pinfunction "1_1") (pintype "passive"))
      (node (ref "U23") (pin "1") (pinfunction "NRESPB5_1") (pintype "passive"))
    )
    (net (code "102") (name "Net-(U25-DS)") (class "Default")
      (node (ref "J1") (pin "2") (pinfunction "2_2") (pintype "passive"))
      (node (ref "U25") (pin "14") (pinfunction "DS_14") (pintype "passive"))
    )
    (net (code "103") (name "Net-(U25-Q7{slash}2)") (class "Default")
      (node (ref "U25") (pin "9") (pinfunction "Q7/2_9") (pintype "passive"))
      (node (ref "U26") (pin "14") (pinfunction "DS_14") (pintype "passive"))
    )
    (net (code "104") (name "Net-(U25-SH{slash}CP)") (class "Default")
      (node (ref "J1") (pin "3") (pinfunction "3_3") (pintype "passive"))
      (node (ref "U25") (pin "11") (pinfunction "SH/CP_11") (pintype "passive"))
      (node (ref "U26") (pin "11") (pinfunction "SH/CP_11") (pintype "passive"))
    )
    (net (code "105") (name "Net-(U25-ST{slash}CP)") (class "Default")
      (node (ref "J1") (pin "4") (pinfunction "4_4") (pintype "passive"))
      (node (ref "U25") (pin "12") (pinfunction "ST/CP_12") (pintype "passive"))
      (node (ref "U26") (pin "12") (pinfunction "ST/CP_12") (pintype "passive"))
    )
    (net (code "106") (name "VCC_Bat") (class "Default")
      (node (ref "C1") (pin "2") (pinfunction "2_2") (pintype "passive"))
      (node (ref "C11") (pin "2") (pinfunction "2_2") (pintype "passive"))
      (node (ref "C13") (pin "2") (pinfunction "2_2") (pintype "passive"))
      (node (ref "C15") (pin "2") (pinfunction "2_2") (pintype "passive"))
      (node (ref "C17") (pin "2") (pinfunction "2_2") (pintype "passive"))
      (node (ref "C19") (pin "2") (pinfunction "2_2") (pintype "passive"))
      (node (ref "C21") (pin "2") (pinfunction "2_2") (pintype "passive"))
      (node (ref "C23") (pin "2") (pinfunction "2_2") (pintype "passive"))
      (node (ref "C26") (pin "2") (pinfunction "2_2") (pintype "passive"))
      (node (ref "C29") (pin "1") (pinfunction "1_1") (pintype "passive"))
      (node (ref "C3") (pin "2") (pinfunction "2_2") (pintype "passive"))
      (node (ref "C30") (pin "1") (pinfunction "1_1") (pintype "passive"))
      (node (ref "C5") (pin "2") (pinfunction "2_2") (pintype "passive"))
      (node (ref "C7") (pin "2") (pinfunction "2_2") (pintype "passive"))
      (node (ref "C9") (pin "2") (pinfunction "2_2") (pintype "passive"))
      (node (ref "D1") (pin "1") (pinfunction "1_1") (pintype "passive"))
      (node (ref "D10") (pin "1") (pinfunction "1_1") (pintype "passive"))
      (node (ref "D11") (pin "1") (pinfunction "1_1") (pintype "passive"))
      (node (ref "D12") (pin "1") (pinfunction "1_1") (pintype "passive"))
      (node (ref "D2") (pin "1") (pinfunction "1_1") (pintype "passive"))
      (node (ref "D3") (pin "1") (pinfunction "1_1") (pintype "passive"))
      (node (ref "D4") (pin "1") (pinfunction "1_1") (pintype "passive"))
      (node (ref "D5") (pin "1") (pinfunction "1_1") (pintype "passive"))
      (node (ref "D6") (pin "1") (pinfunction "1_1") (pintype "passive"))
      (node (ref "D7") (pin "1") (pinfunction "1_1") (pintype "passive"))
      (node (ref "D8") (pin "1") (pinfunction "1_1") (pintype "passive"))
      (node (ref "D9") (pin "1") (pinfunction "1_1") (pintype "passive"))
      (node (ref "P1") (pin "2") (pinfunction "2_2") (pintype "passive"))
      (node (ref "P10") (pin "2") (pinfunction "2_2") (pintype "passive"))
      (node (ref "P11") (pin "2") (pinfunction "2_2") (pintype "passive"))
      (node (ref "P12") (pin "2") (pinfunction "2_2") (pintype "passive"))
      (node (ref "P13") (pin "1") (pinfunction "1_1") (pintype "passive"))
      (node (ref "P2") (pin "2") (pinfunction "2_2") (pintype "passive"))
      (node (ref "P3") (pin "2") (pinfunction "2_2") (pintype "passive"))
      (node (ref "P4") (pin "2") (pinfunction "2_2") (pintype "passive"))
      (node (ref "P5") (pin "2") (pinfunction "2_2") (pintype "passive"))
      (node (ref "P6") (pin "2") (pinfunction "2_2") (pintype "passive"))
      (node (ref "P7") (pin "2") (pinfunction "2_2") (pintype "passive"))
      (node (ref "P8") (pin "2") (pinfunction "2_2") (pintype "passive"))
      (node (ref "P9") (pin "2") (pinfunction "2_2") (pintype "passive"))
      (node (ref "U1") (pin "1") (pinfunction "IN_1") (pintype "passive"))
      (node (ref "U12") (pin "1") (pinfunction "IN_1") (pintype "passive"))
      (node (ref "U13") (pin "1") (pinfunction "IN_1") (pintype "passive"))
      (node (ref "U16") (pin "1") (pinfunction "IN_1") (pintype "passive"))
      (node (ref "U17") (pin "1") (pinfunction "IN_1") (pintype "passive"))
      (node (ref "U20") (pin "1") (pinfunction "IN_1") (pintype "passive"))
      (node (ref "U21") (pin "1") (pinfunction "IN_1") (pintype "passive"))
      (node (ref "U24") (pin "1") (pinfunction "IN_1") (pintype "passive"))
      (node (ref "U27") (pin "1") (pinfunction "IN_1") (pintype "passive"))
      (node (ref "U4") (pin "1") (pinfunction "IN_1") (pintype "passive"))
      (node (ref "U5") (pin "1") (pinfunction "IN_1") (pintype "passive"))
      (node (ref "U8") (pin "1") (pinfunction "IN_1") (pintype "passive"))
      (node (ref "U9") (pin "1") (pinfunction "IN_1") (pintype "passive"))
    )
    (net (code "107") (name "unconnected-(U26-Q4-Pad4)") (class "Default")
      (node (ref "U26") (pin "4") (pinfunction "Q4_4") (pintype "passive+no_connect"))
    )
    (net (code "108") (name "unconnected-(U26-Q5-Pad5)") (class "Default")
      (node (ref "U26") (pin "5") (pinfunction "Q5_5") (pintype "passive+no_connect"))
    )
    (net (code "109") (name "unconnected-(U26-Q6-Pad6)") (class "Default")
      (node (ref "U26") (pin "6") (pinfunction "Q6_6") (pintype "passive+no_connect"))
    )
    (net (code "110") (name "unconnected-(U26-Q7-Pad7)") (class "Default")
      (node (ref "U26") (pin "7") (pinfunction "Q7_7") (pintype "passive+no_connect"))
    )
    (net (code "111") (name "unconnected-(U26-Q7{slash}2-Pad9)") (class "Default")
      (node (ref "U26") (pin "9") (pinfunction "Q7/2_9") (pintype "passive+no_connect"))
    )
  )
)
